# Motherboard.net
KiCad netlist of a schematic drawn in EAGLE
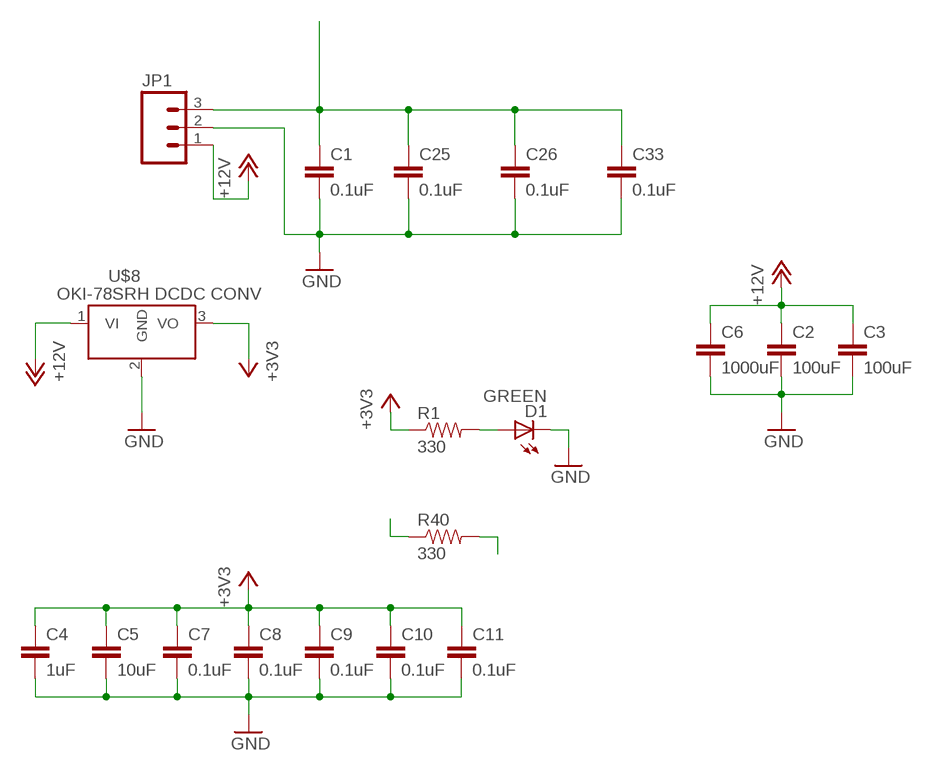
[diagram p0: schematic, sheet 1]
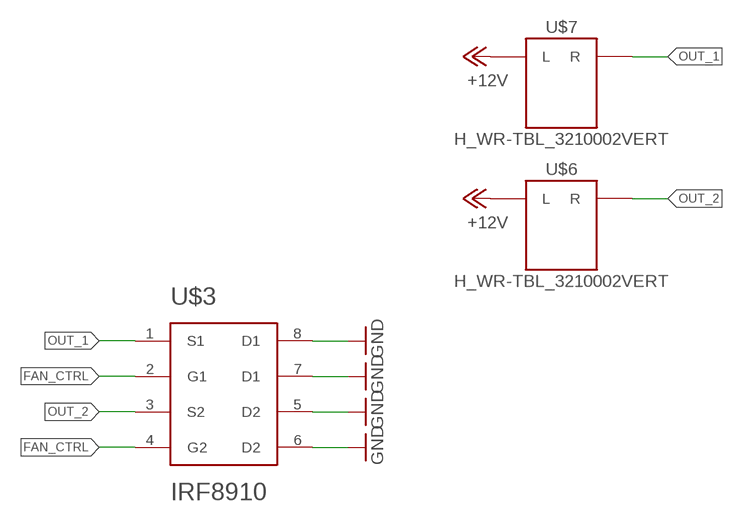
[diagram p1: schematic, sheet 2]
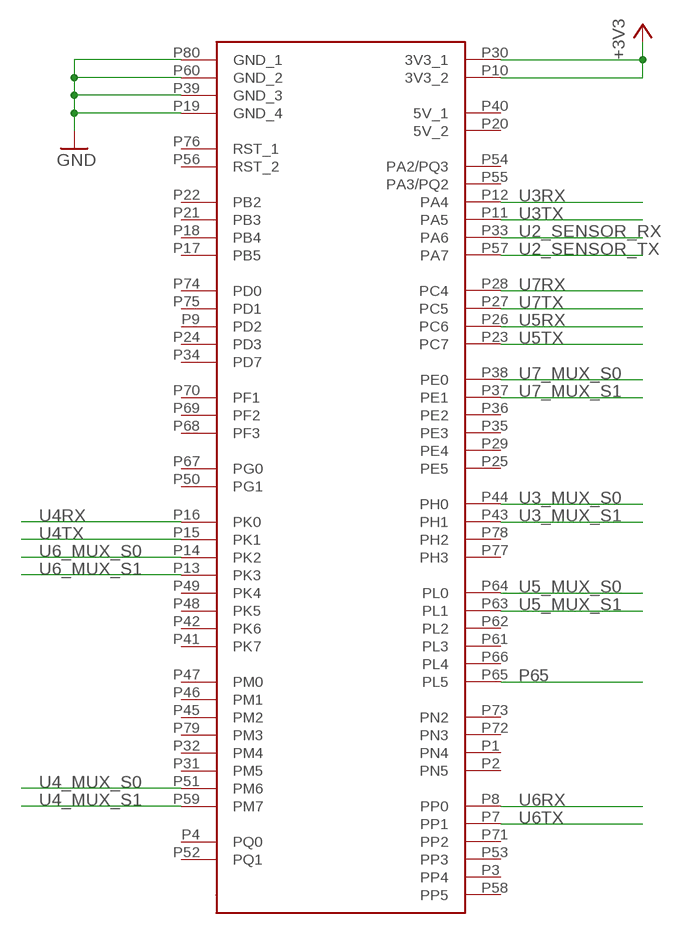
[diagram p2: schematic, sheet 3]
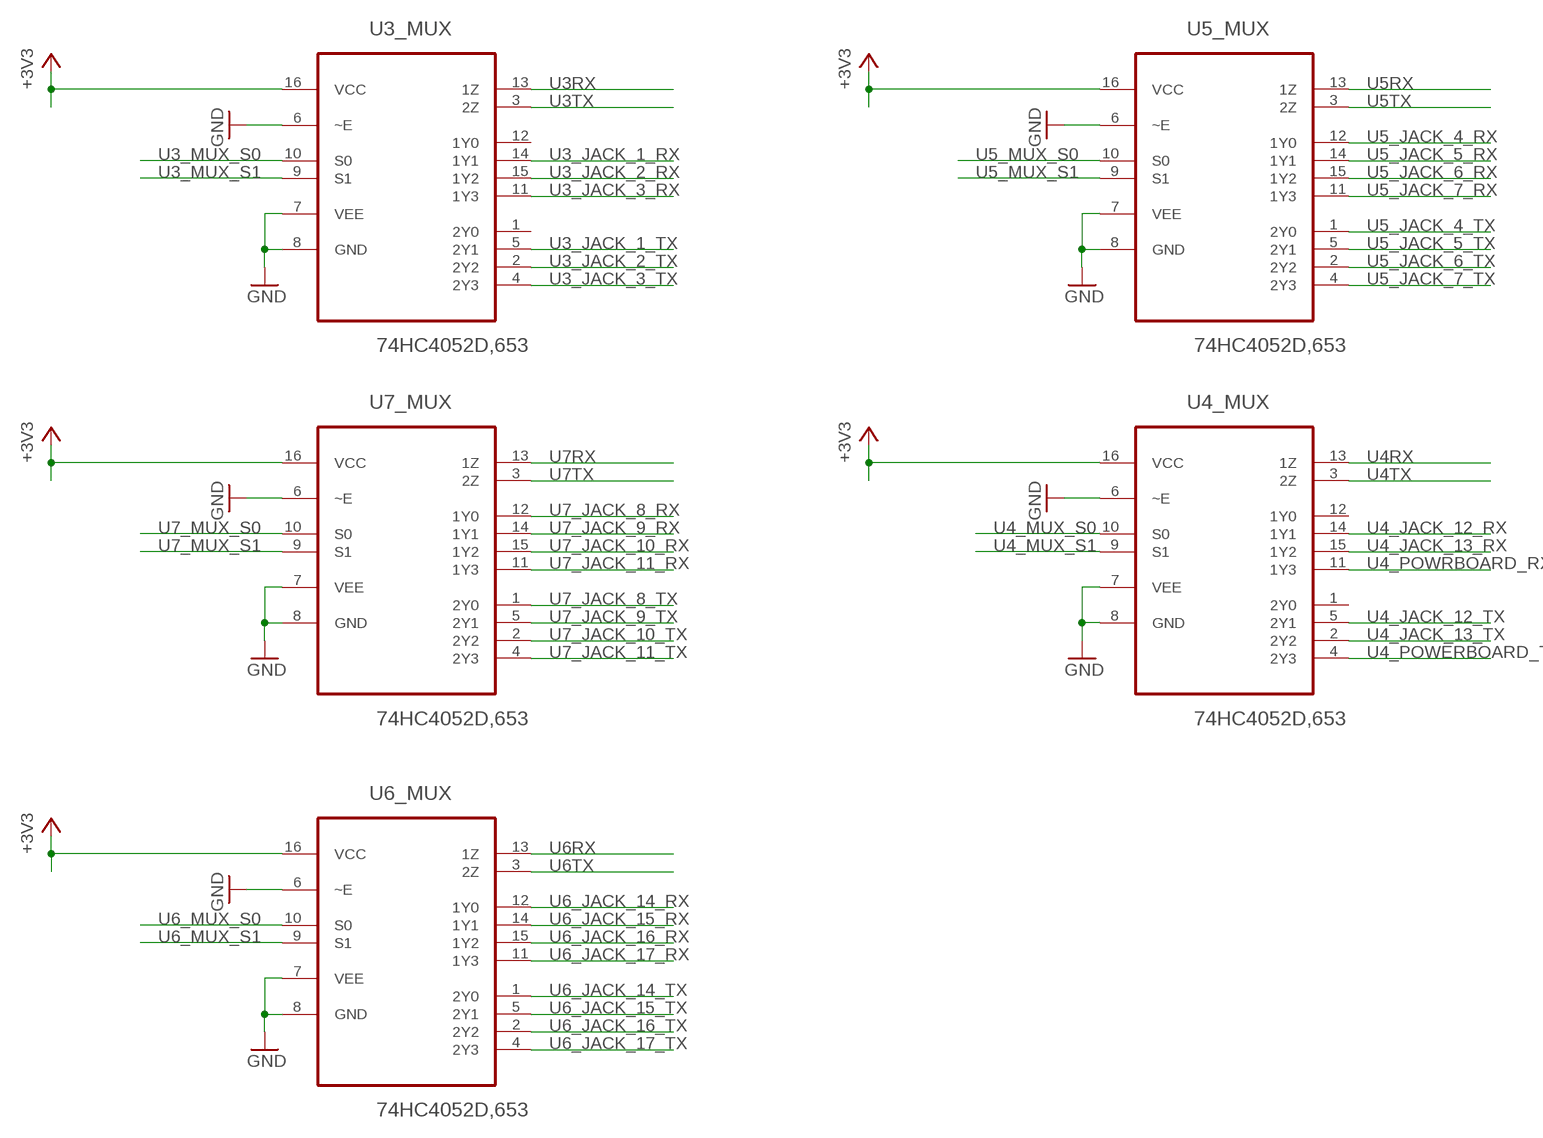
[diagram p3: schematic, sheet 4]
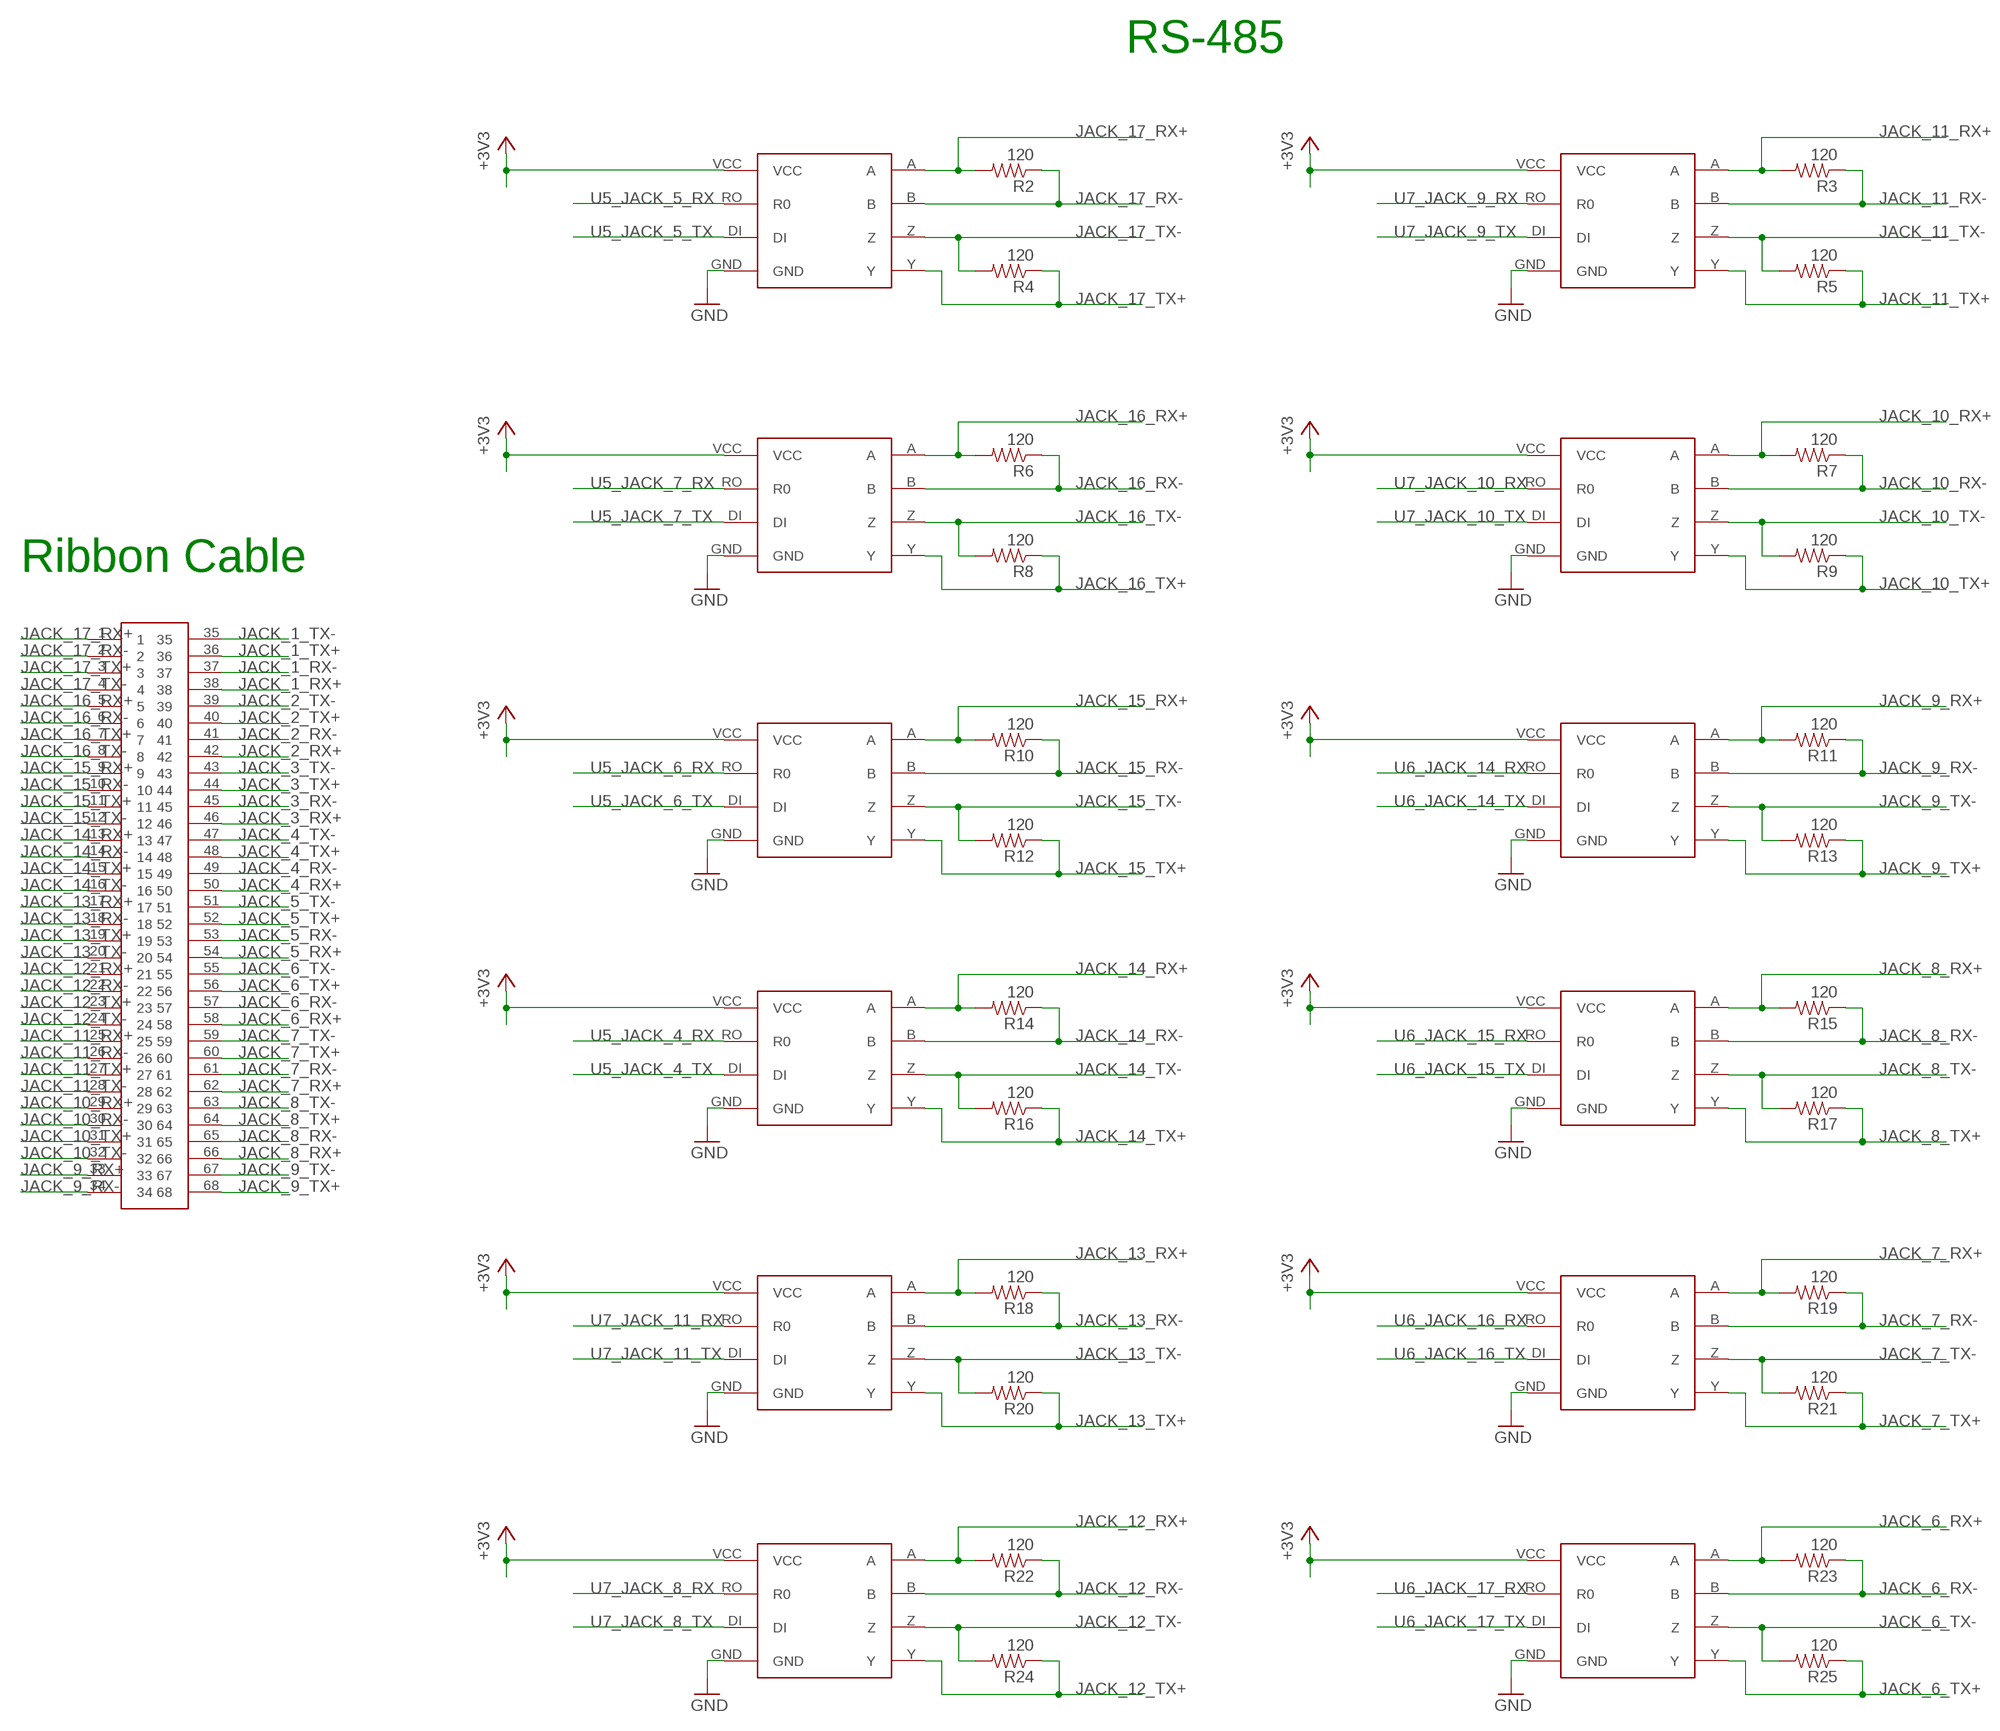
[diagram p4: schematic, sheet 5, part 1 of 2]
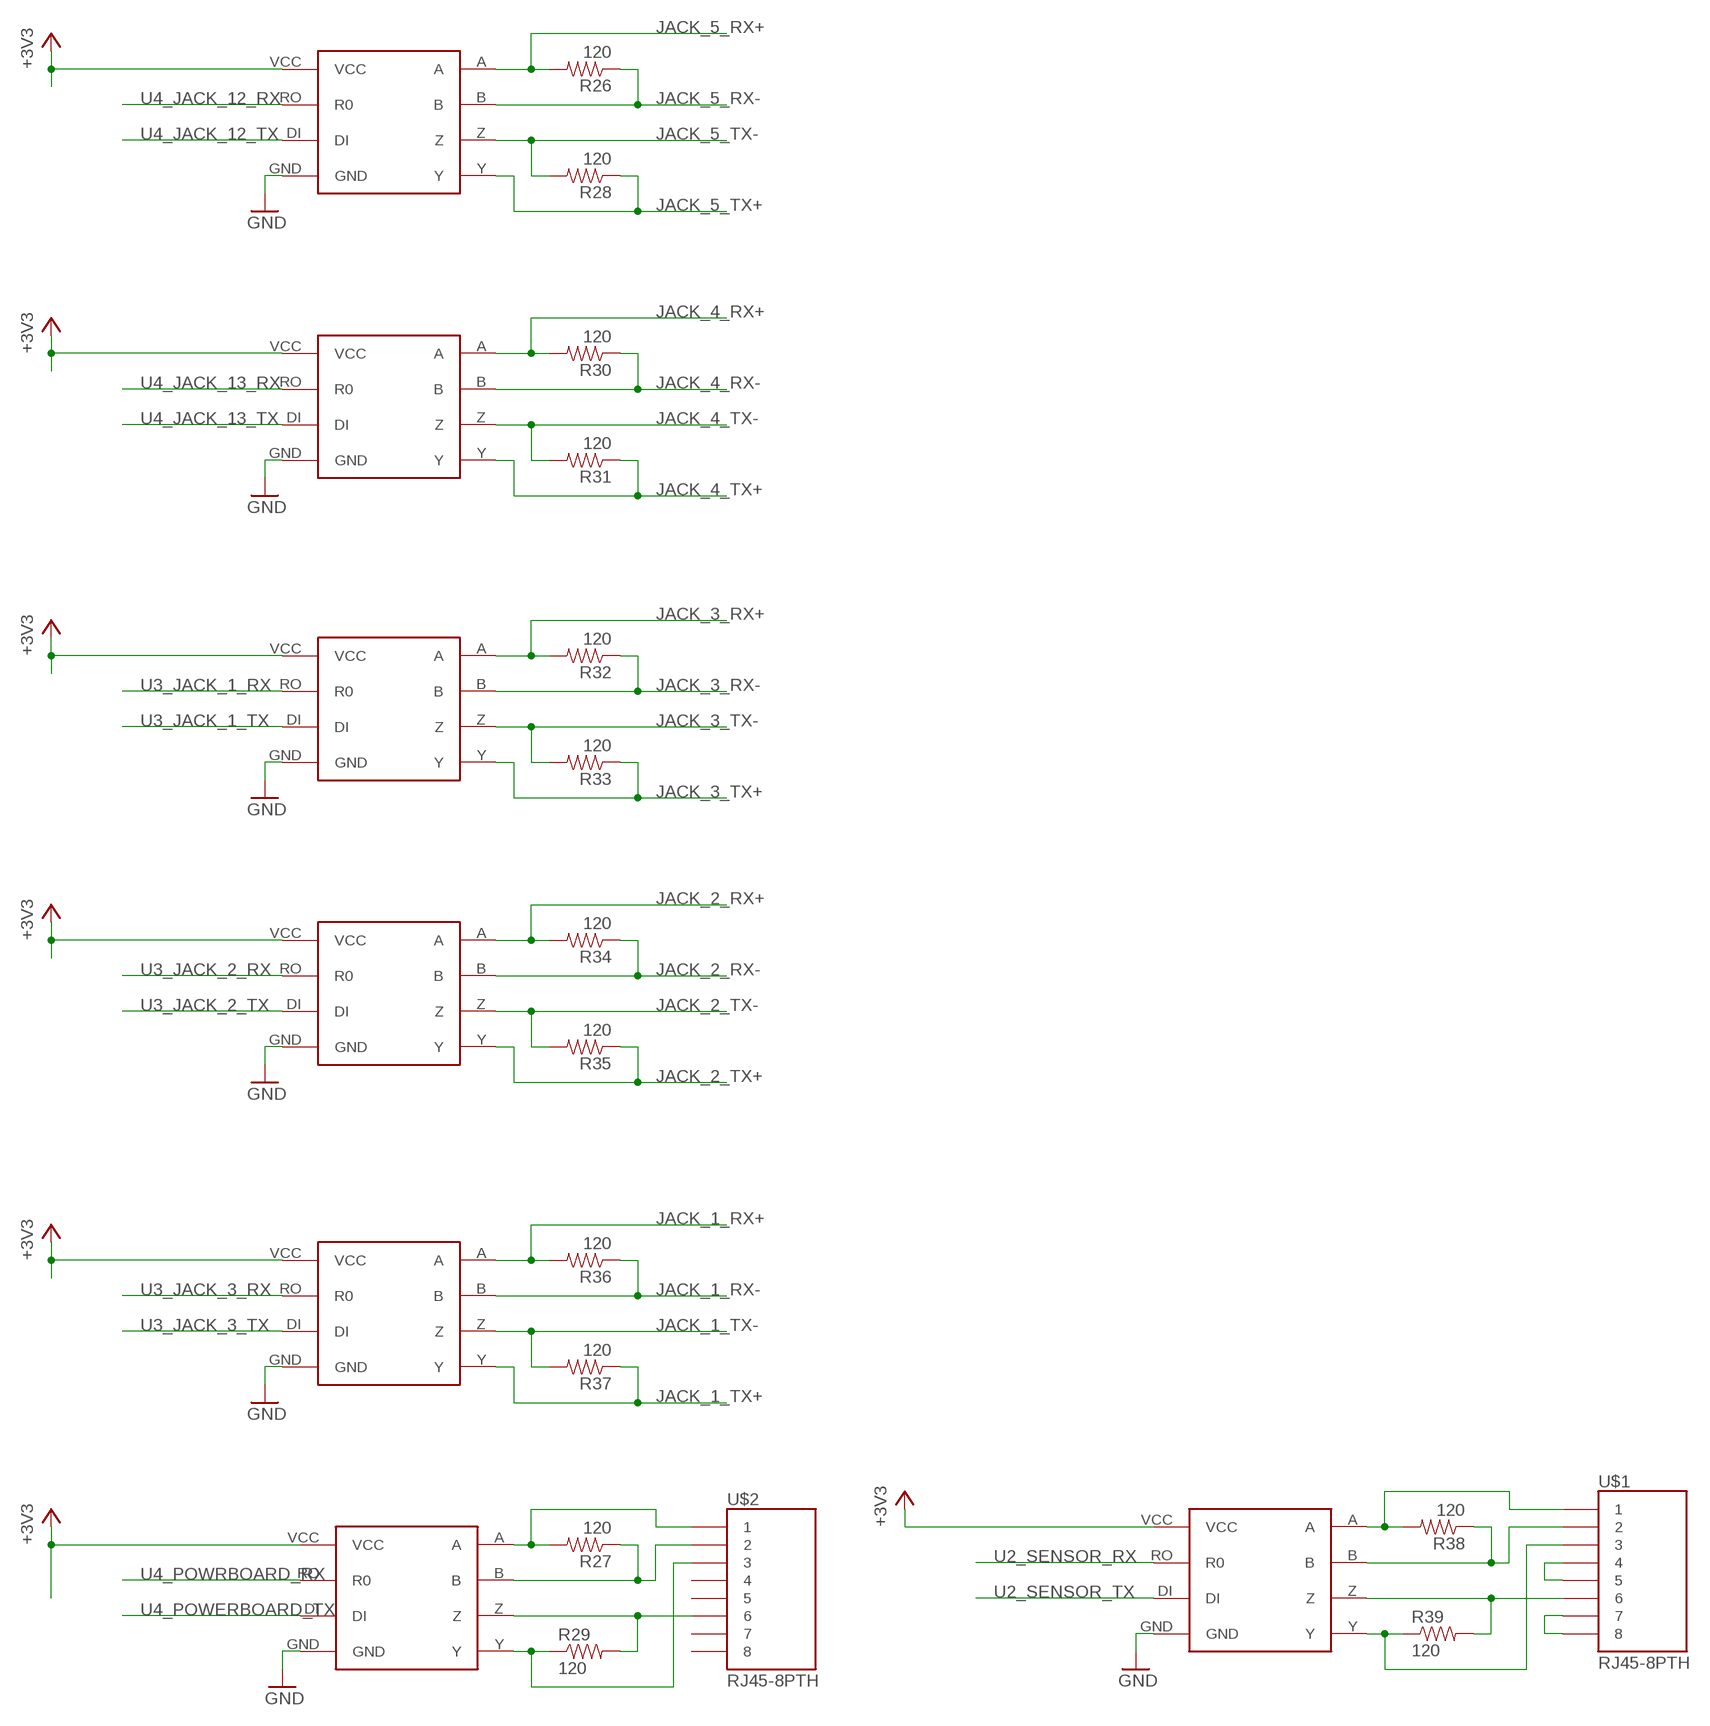
[diagram p5: schematic, sheet 5, part 2 of 2]
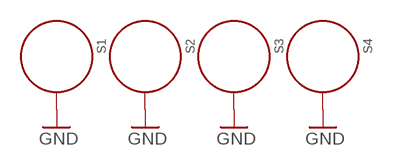
[diagram p6: schematic, sheet 6]

(export (version "E")
  (design (tool "Eeschema 10.0.6"))
  (components
    (comp (ref "S1")
      (value "STANDOFF_ELECTRICAL")
      (footprint "eagle-import:STANDOFF-ELECTRICAL")
      (libsource (lib "eagle-import") (part "STANDOFF_ELECTRICAL"))
    )
    (comp (ref "S2")
      (value "STANDOFF_ELECTRICAL")
      (footprint "eagle-import:STANDOFF-ELECTRICAL")
      (libsource (lib "eagle-import") (part "STANDOFF_ELECTRICAL"))
    )
    (comp (ref "S3")
      (value "STANDOFF_ELECTRICAL")
      (footprint "eagle-import:STANDOFF-ELECTRICAL")
      (libsource (lib "eagle-import") (part "STANDOFF_ELECTRICAL"))
    )
    (comp (ref "S4")
      (value "STANDOFF_ELECTRICAL")
      (footprint "eagle-import:STANDOFF-ELECTRICAL")
      (libsource (lib "eagle-import") (part "STANDOFF_ELECTRICAL"))
    )
    (comp (ref "R2")
      (value "120")
      (footprint "eagle-import:1206")
      (libsource (lib "eagle-import") (part "RESISTOR1206"))
    )
    (comp (ref "R3")
      (value "120")
      (footprint "eagle-import:1206")
      (libsource (lib "eagle-import") (part "RESISTOR1206"))
    )
    (comp (ref "R4")
      (value "120")
      (footprint "eagle-import:1206")
      (libsource (lib "eagle-import") (part "RESISTOR1206"))
    )
    (comp (ref "R5")
      (value "120")
      (footprint "eagle-import:1206")
      (libsource (lib "eagle-import") (part "RESISTOR1206"))
    )
    (comp (ref "R6")
      (value "120")
      (footprint "eagle-import:1206")
      (libsource (lib "eagle-import") (part "RESISTOR1206"))
    )
    (comp (ref "R7")
      (value "120")
      (footprint "eagle-import:1206")
      (libsource (lib "eagle-import") (part "RESISTOR1206"))
    )
    (comp (ref "R8")
      (value "120")
      (footprint "eagle-import:1206")
      (libsource (lib "eagle-import") (part "RESISTOR1206"))
    )
    (comp (ref "R9")
      (value "120")
      (footprint "eagle-import:1206")
      (libsource (lib "eagle-import") (part "RESISTOR1206"))
    )
    (comp (ref "R10")
      (value "120")
      (footprint "eagle-import:1206")
      (libsource (lib "eagle-import") (part "RESISTOR1206"))
    )
    (comp (ref "R11")
      (value "120")
      (footprint "eagle-import:1206")
      (libsource (lib "eagle-import") (part "RESISTOR1206"))
    )
    (comp (ref "R12")
      (value "120")
      (footprint "eagle-import:1206")
      (libsource (lib "eagle-import") (part "RESISTOR1206"))
    )
    (comp (ref "R13")
      (value "120")
      (footprint "eagle-import:1206")
      (libsource (lib "eagle-import") (part "RESISTOR1206"))
    )
    (comp (ref "R14")
      (value "120")
      (footprint "eagle-import:1206")
      (libsource (lib "eagle-import") (part "RESISTOR1206"))
    )
    (comp (ref "R15")
      (value "120")
      (footprint "eagle-import:1206")
      (libsource (lib "eagle-import") (part "RESISTOR1206"))
    )
    (comp (ref "R16")
      (value "120")
      (footprint "eagle-import:1206")
      (libsource (lib "eagle-import") (part "RESISTOR1206"))
    )
    (comp (ref "R17")
      (value "120")
      (footprint "eagle-import:1206")
      (libsource (lib "eagle-import") (part "RESISTOR1206"))
    )
    (comp (ref "R18")
      (value "120")
      (footprint "eagle-import:1206")
      (libsource (lib "eagle-import") (part "RESISTOR1206"))
    )
    (comp (ref "R19")
      (value "120")
      (footprint "eagle-import:1206")
      (libsource (lib "eagle-import") (part "RESISTOR1206"))
    )
    (comp (ref "R20")
      (value "120")
      (footprint "eagle-import:1206")
      (libsource (lib "eagle-import") (part "RESISTOR1206"))
    )
    (comp (ref "R21")
      (value "120")
      (footprint "eagle-import:1206")
      (libsource (lib "eagle-import") (part "RESISTOR1206"))
    )
    (comp (ref "R22")
      (value "120")
      (footprint "eagle-import:1206")
      (libsource (lib "eagle-import") (part "RESISTOR1206"))
    )
    (comp (ref "R23")
      (value "120")
      (footprint "eagle-import:1206")
      (libsource (lib "eagle-import") (part "RESISTOR1206"))
    )
    (comp (ref "R24")
      (value "120")
      (footprint "eagle-import:1206")
      (libsource (lib "eagle-import") (part "RESISTOR1206"))
    )
    (comp (ref "R25")
      (value "120")
      (footprint "eagle-import:1206")
      (libsource (lib "eagle-import") (part "RESISTOR1206"))
    )
    (comp (ref "R26")
      (value "120")
      (footprint "eagle-import:1206")
      (libsource (lib "eagle-import") (part "RESISTOR1206"))
    )
    (comp (ref "R27")
      (value "120")
      (footprint "eagle-import:1206")
      (libsource (lib "eagle-import") (part "RESISTOR1206"))
    )
    (comp (ref "R28")
      (value "120")
      (footprint "eagle-import:1206")
      (libsource (lib "eagle-import") (part "RESISTOR1206"))
    )
    (comp (ref "R29")
      (value "120")
      (footprint "eagle-import:1206")
      (libsource (lib "eagle-import") (part "RESISTOR1206"))
    )
    (comp (ref "R30")
      (value "120")
      (footprint "eagle-import:1206")
      (libsource (lib "eagle-import") (part "RESISTOR1206"))
    )
    (comp (ref "R31")
      (value "120")
      (footprint "eagle-import:1206")
      (libsource (lib "eagle-import") (part "RESISTOR1206"))
    )
    (comp (ref "R32")
      (value "120")
      (footprint "eagle-import:1206")
      (libsource (lib "eagle-import") (part "RESISTOR1206"))
    )
    (comp (ref "R33")
      (value "120")
      (footprint "eagle-import:1206")
      (libsource (lib "eagle-import") (part "RESISTOR1206"))
    )
    (comp (ref "R34")
      (value "120")
      (footprint "eagle-import:1206")
      (libsource (lib "eagle-import") (part "RESISTOR1206"))
    )
    (comp (ref "R35")
      (value "120")
      (footprint "eagle-import:1206")
      (libsource (lib "eagle-import") (part "RESISTOR1206"))
    )
    (comp (ref "R36")
      (value "120")
      (footprint "eagle-import:1206")
      (libsource (lib "eagle-import") (part "RESISTOR1206"))
    )
    (comp (ref "R37")
      (value "120")
      (footprint "eagle-import:1206")
      (libsource (lib "eagle-import") (part "RESISTOR1206"))
    )
    (comp (ref "R38")
      (value "120")
      (footprint "eagle-import:1206")
      (libsource (lib "eagle-import") (part "RESISTOR1206"))
    )
    (comp (ref "R39")
      (value "120")
      (footprint "eagle-import:1206")
      (libsource (lib "eagle-import") (part "RESISTOR1206"))
    )
    (comp (ref "RS-485-1")
      (value "MAX3077")
      (footprint "eagle-import:MAX3070E")
      (libsource (lib "eagle-import") (part "MAX3077"))
    )
    (comp (ref "RS-485-2")
      (value "MAX3077")
      (footprint "eagle-import:MAX3070E")
      (libsource (lib "eagle-import") (part "MAX3077"))
    )
    (comp (ref "RS_TRANS_1")
      (value "MAX3077")
      (footprint "eagle-import:MAX3070E")
      (libsource (lib "eagle-import") (part "MAX3077"))
    )
    (comp (ref "RS_TRANS_2")
      (value "MAX3077")
      (footprint "eagle-import:MAX3070E")
      (libsource (lib "eagle-import") (part "MAX3077"))
    )
    (comp (ref "RS_TRANS_3")
      (value "MAX3077")
      (footprint "eagle-import:MAX3070E")
      (libsource (lib "eagle-import") (part "MAX3077"))
    )
    (comp (ref "RS_TRANS_4")
      (value "MAX3077")
      (footprint "eagle-import:MAX3070E")
      (libsource (lib "eagle-import") (part "MAX3077"))
    )
    (comp (ref "RS_TRANS_5")
      (value "MAX3077")
      (footprint "eagle-import:MAX3070E")
      (libsource (lib "eagle-import") (part "MAX3077"))
    )
    (comp (ref "RS_TRANS_6")
      (value "MAX3077")
      (footprint "eagle-import:MAX3070E")
      (libsource (lib "eagle-import") (part "MAX3077"))
    )
    (comp (ref "RS_TRANS_7")
      (value "MAX3077")
      (footprint "eagle-import:MAX3070E")
      (libsource (lib "eagle-import") (part "MAX3077"))
    )
    (comp (ref "RS_TRANS_8")
      (value "MAX3077")
      (footprint "eagle-import:MAX3070E")
      (libsource (lib "eagle-import") (part "MAX3077"))
    )
    (comp (ref "RS_TRANS_9")
      (value "MAX3077")
      (footprint "eagle-import:MAX3070E")
      (libsource (lib "eagle-import") (part "MAX3077"))
    )
    (comp (ref "RS_TRANS_10")
      (value "MAX3077")
      (footprint "eagle-import:MAX3070E")
      (libsource (lib "eagle-import") (part "MAX3077"))
    )
    (comp (ref "RS_TRANS_11")
      (value "MAX3077")
      (footprint "eagle-import:MAX3070E")
      (libsource (lib "eagle-import") (part "MAX3077"))
    )
    (comp (ref "RS_TRANS_12")
      (value "MAX3077")
      (footprint "eagle-import:MAX3070E")
      (libsource (lib "eagle-import") (part "MAX3077"))
    )
    (comp (ref "RS_TRANS_13")
      (value "MAX3077")
      (footprint "eagle-import:MAX3070E")
      (libsource (lib "eagle-import") (part "MAX3077"))
    )
    (comp (ref "RS_TRANS_14")
      (value "MAX3077")
      (footprint "eagle-import:MAX3070E")
      (libsource (lib "eagle-import") (part "MAX3077"))
    )
    (comp (ref "RS_TRANS_15")
      (value "MAX3077")
      (footprint "eagle-import:MAX3070E")
      (libsource (lib "eagle-import") (part "MAX3077"))
    )
    (comp (ref "RS_TRANS_16")
      (value "MAX3077")
      (footprint "eagle-import:MAX3070E")
      (libsource (lib "eagle-import") (part "MAX3077"))
    )
    (comp (ref "RS_TRANS_17")
      (value "MAX3077")
      (footprint "eagle-import:MAX3070E")
      (libsource (lib "eagle-import") (part "MAX3077"))
    )
    (comp (ref "U$1")
      (value "RJ45-8PTH")
      (footprint "eagle-import:RJ45-8")
      (libsource (lib "eagle-import") (part "RJ45-8PTH"))
    )
    (comp (ref "U$2")
      (value "RJ45-8PTH")
      (footprint "eagle-import:RJ45-8")
      (libsource (lib "eagle-import") (part "RJ45-8PTH"))
    )
    (comp (ref "U$4")
      (value "TB60050685100")
      (footprint "eagle-import:60050685100")
      (libsource (lib "eagle-import") (part "TB60050685100"))
    )
    (comp (ref "C1")
      (value "0.1uF")
      (footprint "eagle-import:1206")
      (libsource (lib "eagle-import") (part "CAP1206"))
    )
    (comp (ref "C2")
      (value "100uF")
      (footprint "eagle-import:1206")
      (libsource (lib "eagle-import") (part "CAP1206"))
    )
    (comp (ref "C3")
      (value "100uF")
      (footprint "eagle-import:1206")
      (libsource (lib "eagle-import") (part "CAP1206"))
    )
    (comp (ref "C4")
      (value "1uF")
      (footprint "eagle-import:1206")
      (libsource (lib "eagle-import") (part "CAP1206"))
    )
    (comp (ref "C5")
      (value "10uF")
      (footprint "eagle-import:1206")
      (libsource (lib "eagle-import") (part "CAP1206"))
    )
    (comp (ref "C6")
      (value "1000uF")
      (footprint "eagle-import:1206")
      (libsource (lib "eagle-import") (part "CAP1206"))
    )
    (comp (ref "C7")
      (value "0.1uF")
      (footprint "eagle-import:1206")
      (libsource (lib "eagle-import") (part "CAP1206"))
    )
    (comp (ref "C8")
      (value "0.1uF")
      (footprint "eagle-import:1206")
      (libsource (lib "eagle-import") (part "CAP1206"))
    )
    (comp (ref "C9")
      (value "0.1uF")
      (footprint "eagle-import:1206")
      (libsource (lib "eagle-import") (part "CAP1206"))
    )
    (comp (ref "C10")
      (value "0.1uF")
      (footprint "eagle-import:1206")
      (libsource (lib "eagle-import") (part "CAP1206"))
    )
    (comp (ref "C11")
      (value "0.1uF")
      (footprint "eagle-import:1206")
      (libsource (lib "eagle-import") (part "CAP1206"))
    )
    (comp (ref "C25")
      (value "0.1uF")
      (footprint "eagle-import:1206")
      (libsource (lib "eagle-import") (part "CAP1206"))
    )
    (comp (ref "C26")
      (value "0.1uF")
      (footprint "eagle-import:1206")
      (libsource (lib "eagle-import") (part "CAP1206"))
    )
    (comp (ref "C33")
      (value "0.1uF")
      (footprint "eagle-import:1206")
      (libsource (lib "eagle-import") (part "CAP1206"))
    )
    (comp (ref "D1")
      (value "GREEN")
      (footprint "eagle-import:LED-1206")
      (libsource (lib "eagle-import") (part "LED-GREENLARGE"))
    )
    (comp (ref "JP1")
      (value "M03SCREW")
      (footprint "eagle-import:SCREWTERMINAL-3.5MM-3")
      (libsource (lib "eagle-import") (part "M03SCREW"))
    )
    (comp (ref "R1")
      (value "330")
      (footprint "eagle-import:1206")
      (libsource (lib "eagle-import") (part "RESISTOR1206"))
    )
    (comp (ref "R40")
      (value "330")
      (footprint "eagle-import:1206")
      (libsource (lib "eagle-import") (part "RESISTOR1206"))
    )
    (comp (ref "U$8")
      (value "Q_OKI-78SR")
      (footprint "eagle-import:OKI-78SRH")
      (libsource (lib "eagle-import") (part "Q_OKI-78SR"))
    )
    (comp (ref "U$3")
      (value "IRF8910")
      (footprint "eagle-import:SO8")
      (libsource (lib "eagle-import") (part "IRF8910"))
    )
    (comp (ref "U$6")
      (value "H_WR-TBL_3210002VERT")
      (footprint "eagle-import:691321100002")
      (libsource (lib "eagle-import") (part "H_WR-TBL_3210002VERT"))
    )
    (comp (ref "U$7")
      (value "H_WR-TBL_3210002VERT")
      (footprint "eagle-import:691321100002")
      (libsource (lib "eagle-import") (part "H_WR-TBL_3210002VERT"))
    )
    (comp (ref "U3_MUX")
      (value "74HC4052D,653")
      (footprint "eagle-import:SOIC127P600X175-16N")
      (libsource (lib "eagle-import") (part "74HC4052D,653"))
    )
    (comp (ref "U4_MUX")
      (value "74HC4052D,653")
      (footprint "eagle-import:SOIC127P600X175-16N")
      (libsource (lib "eagle-import") (part "74HC4052D,653"))
    )
    (comp (ref "U5_MUX")
      (value "74HC4052D,653")
      (footprint "eagle-import:SOIC127P600X175-16N")
      (libsource (lib "eagle-import") (part "74HC4052D,653"))
    )
    (comp (ref "U6_MUX")
      (value "74HC4052D,653")
      (footprint "eagle-import:SOIC127P600X175-16N")
      (libsource (lib "eagle-import") (part "74HC4052D,653"))
    )
    (comp (ref "U7_MUX")
      (value "74HC4052D,653")
      (footprint "eagle-import:SOIC127P600X175-16N")
      (libsource (lib "eagle-import") (part "74HC4052D,653"))
    )
    (comp (ref "U$5")
      (value "STELLARISLAUNCHPAD_CONNECTED")
      (footprint "eagle-import:STELLARISLAUNCHPAD_CONNECTED")
      (libsource (lib "eagle-import") (part "STELLARISLAUNCHPAD_CONNECTED"))
    )
  )
  (nets
    (net (code "1") (name "+3V3") (class "Default")
      (node (ref "C10") (pin "1") (pinfunction "1_1") (pintype "passive"))
      (node (ref "C11") (pin "1") (pinfunction "1_1") (pintype "passive"))
      (node (ref "C4") (pin "1") (pinfunction "1_1") (pintype "passive"))
      (node (ref "C5") (pin "1") (pinfunction "1_1") (pintype "passive"))
      (node (ref "C7") (pin "1") (pinfunction "1_1") (pintype "passive"))
      (node (ref "C8") (pin "1") (pinfunction "1_1") (pintype "passive"))
      (node (ref "C9") (pin "1") (pinfunction "1_1") (pintype "passive"))
      (node (ref "R1") (pin "1") (pinfunction "1_1") (pintype "passive"))
      (node (ref "RS-485-1") (pin "VCC") (pinfunction "VCC_VCC") (pintype "bidirectional"))
      (node (ref "RS-485-2") (pin "VCC") (pinfunction "VCC_VCC") (pintype "bidirectional"))
      (node (ref "RS_TRANS_1") (pin "VCC") (pinfunction "VCC_VCC") (pintype "bidirectional"))
      (node (ref "RS_TRANS_10") (pin "VCC") (pinfunction "VCC_VCC") (pintype "bidirectional"))
      (node (ref "RS_TRANS_11") (pin "VCC") (pinfunction "VCC_VCC") (pintype "bidirectional"))
      (node (ref "RS_TRANS_12") (pin "VCC") (pinfunction "VCC_VCC") (pintype "bidirectional"))
      (node (ref "RS_TRANS_13") (pin "VCC") (pinfunction "VCC_VCC") (pintype "bidirectional"))
      (node (ref "RS_TRANS_14") (pin "VCC") (pinfunction "VCC_VCC") (pintype "bidirectional"))
      (node (ref "RS_TRANS_15") (pin "VCC") (pinfunction "VCC_VCC") (pintype "bidirectional"))
      (node (ref "RS_TRANS_16") (pin "VCC") (pinfunction "VCC_VCC") (pintype "bidirectional"))
      (node (ref "RS_TRANS_17") (pin "VCC") (pinfunction "VCC_VCC") (pintype "bidirectional"))
      (node (ref "RS_TRANS_2") (pin "VCC") (pinfunction "VCC_VCC") (pintype "bidirectional"))
      (node (ref "RS_TRANS_3") (pin "VCC") (pinfunction "VCC_VCC") (pintype "bidirectional"))
      (node (ref "RS_TRANS_4") (pin "VCC") (pinfunction "VCC_VCC") (pintype "bidirectional"))
      (node (ref "RS_TRANS_5") (pin "VCC") (pinfunction "VCC_VCC") (pintype "bidirectional"))
      (node (ref "RS_TRANS_6") (pin "VCC") (pinfunction "VCC_VCC") (pintype "bidirectional"))
      (node (ref "RS_TRANS_7") (pin "VCC") (pinfunction "VCC_VCC") (pintype "bidirectional"))
      (node (ref "RS_TRANS_8") (pin "VCC") (pinfunction "VCC_VCC") (pintype "bidirectional"))
      (node (ref "RS_TRANS_9") (pin "VCC") (pinfunction "VCC_VCC") (pintype "bidirectional"))
      (node (ref "U$5") (pin "P10") (pinfunction "3V3_2_P10") (pintype "bidirectional"))
      (node (ref "U$5") (pin "P30") (pinfunction "3V3_1_P30") (pintype "bidirectional"))
      (node (ref "U$8") (pin "3") (pinfunction "VO_3") (pintype "bidirectional"))
      (node (ref "U3_MUX") (pin "16") (pinfunction "VCC_16") (pintype "power_in"))
      (node (ref "U4_MUX") (pin "16") (pinfunction "VCC_16") (pintype "power_in"))
      (node (ref "U5_MUX") (pin "16") (pinfunction "VCC_16") (pintype "power_in"))
      (node (ref "U6_MUX") (pin "16") (pinfunction "VCC_16") (pintype "power_in"))
      (node (ref "U7_MUX") (pin "16") (pinfunction "VCC_16") (pintype "power_in"))
    )
    (net (code "2") (name "+12V") (class "Default")
      (node (ref "C2") (pin "1") (pinfunction "1_1") (pintype "passive"))
      (node (ref "C3") (pin "1") (pinfunction "1_1") (pintype "passive"))
      (node (ref "C6") (pin "1") (pinfunction "1_1") (pintype "passive"))
      (node (ref "JP1") (pin "1") (pinfunction "1_1") (pintype "passive"))
      (node (ref "U$6") (pin "L") (pinfunction "L_L") (pintype "bidirectional"))
      (node (ref "U$7") (pin "L") (pinfunction "L_L") (pintype "bidirectional"))
      (node (ref "U$8") (pin "1") (pinfunction "VI_1") (pintype "bidirectional"))
    )
    (net (code "3") (name "5V") (class "Default")
      (node (ref "C1") (pin "1") (pinfunction "1_1") (pintype "passive"))
      (node (ref "C25") (pin "1") (pinfunction "1_1") (pintype "passive"))
      (node (ref "C26") (pin "1") (pinfunction "1_1") (pintype "passive"))
      (node (ref "C33") (pin "1") (pinfunction "1_1") (pintype "passive"))
      (node (ref "JP1") (pin "3") (pinfunction "3_3") (pintype "passive"))
      (node (ref "U$1") (pin "4") (pinfunction "4_4") (pintype "bidirectional"))
      (node (ref "U$1") (pin "5") (pinfunction "5_5") (pintype "bidirectional"))
    )
    (net (code "4") (name "FAN_CTRL") (class "Default")
      (node (ref "R40") (pin "2") (pinfunction "2_2") (pintype "passive"))
      (node (ref "U$3") (pin "2") (pinfunction "G1_2") (pintype "bidirectional"))
      (node (ref "U$3") (pin "4") (pinfunction "G2_4") (pintype "bidirectional"))
    )
    (net (code "5") (name "GND") (class "Default")
      (node (ref "C1") (pin "2") (pinfunction "2_2") (pintype "passive"))
      (node (ref "C10") (pin "2") (pinfunction "2_2") (pintype "passive"))
      (node (ref "C11") (pin "2") (pinfunction "2_2") (pintype "passive"))
      (node (ref "C2") (pin "2") (pinfunction "2_2") (pintype "passive"))
      (node (ref "C25") (pin "2") (pinfunction "2_2") (pintype "passive"))
      (node (ref "C26") (pin "2") (pinfunction "2_2") (pintype "passive"))
      (node (ref "C3") (pin "2") (pinfunction "2_2") (pintype "passive"))
      (node (ref "C33") (pin "2") (pinfunction "2_2") (pintype "passive"))
      (node (ref "C4") (pin "2") (pinfunction "2_2") (pintype "passive"))
      (node (ref "C5") (pin "2") (pinfunction "2_2") (pintype "passive"))
      (node (ref "C6") (pin "2") (pinfunction "2_2") (pintype "passive"))
      (node (ref "C7") (pin "2") (pinfunction "2_2") (pintype "passive"))
      (node (ref "C8") (pin "2") (pinfunction "2_2") (pintype "passive"))
      (node (ref "C9") (pin "2") (pinfunction "2_2") (pintype "passive"))
      (node (ref "D1") (pin "C") (pinfunction "C_C") (pintype "passive"))
      (node (ref "JP1") (pin "2") (pinfunction "2_2") (pintype "passive"))
      (node (ref "RS-485-1") (pin "GND") (pinfunction "GND_GND") (pintype "bidirectional"))
      (node (ref "RS-485-2") (pin "GND") (pinfunction "GND_GND") (pintype "bidirectional"))
      (node (ref "RS_TRANS_1") (pin "GND") (pinfunction "GND_GND") (pintype "bidirectional"))
      (node (ref "RS_TRANS_10") (pin "GND") (pinfunction "GND_GND") (pintype "bidirectional"))
      (node (ref "RS_TRANS_11") (pin "GND") (pinfunction "GND_GND") (pintype "bidirectional"))
      (node (ref "RS_TRANS_12") (pin "GND") (pinfunction "GND_GND") (pintype "bidirectional"))
      (node (ref "RS_TRANS_13") (pin "GND") (pinfunction "GND_GND") (pintype "bidirectional"))
      (node (ref "RS_TRANS_14") (pin "GND") (pinfunction "GND_GND") (pintype "bidirectional"))
      (node (ref "RS_TRANS_15") (pin "GND") (pinfunction "GND_GND") (pintype "bidirectional"))
      (node (ref "RS_TRANS_16") (pin "GND") (pinfunction "GND_GND") (pintype "bidirectional"))
      (node (ref "RS_TRANS_17") (pin "GND") (pinfunction "GND_GND") (pintype "bidirectional"))
      (node (ref "RS_TRANS_2") (pin "GND") (pinfunction "GND_GND") (pintype "bidirectional"))
      (node (ref "RS_TRANS_3") (pin "GND") (pinfunction "GND_GND") (pintype "bidirectional"))
      (node (ref "RS_TRANS_4") (pin "GND") (pinfunction "GND_GND") (pintype "bidirectional"))
      (node (ref "RS_TRANS_5") (pin "GND") (pinfunction "GND_GND") (pintype "bidirectional"))
      (node (ref "RS_TRANS_6") (pin "GND") (pinfunction "GND_GND") (pintype "bidirectional"))
      (node (ref "RS_TRANS_7") (pin "GND") (pinfunction "GND_GND") (pintype "bidirectional"))
      (node (ref "RS_TRANS_8") (pin "GND") (pinfunction "GND_GND") (pintype "bidirectional"))
      (node (ref "RS_TRANS_9") (pin "GND") (pinfunction "GND_GND") (pintype "bidirectional"))
      (node (ref "S1") (pin "P1") (pinfunction "P$1_P1") (pintype "bidirectional"))
      (node (ref "S2") (pin "P1") (pinfunction "P$1_P1") (pintype "bidirectional"))
      (node (ref "S3") (pin "P1") (pinfunction "P$1_P1") (pintype "bidirectional"))
      (node (ref "S4") (pin "P1") (pinfunction "P$1_P1") (pintype "bidirectional"))
      (node (ref "U$1") (pin "7") (pinfunction "7_7") (pintype "bidirectional"))
      (node (ref "U$1") (pin "8") (pinfunction "8_8") (pintype "bidirectional"))
      (node (ref "U$3") (pin "5") (pinfunction "D2_5") (pintype "bidirectional"))
      (node (ref "U$3") (pin "6") (pinfunction "D2_6") (pintype "bidirectional"))
      (node (ref "U$3") (pin "7") (pinfunction "D1_7") (pintype "bidirectional"))
      (node (ref "U$3") (pin "8") (pinfunction "D1_8") (pintype "bidirectional"))
      (node (ref "U$5") (pin "P19") (pinfunction "GND_4_P19") (pintype "bidirectional"))
      (node (ref "U$5") (pin "P39") (pinfunction "GND_3_P39") (pintype "bidirectional"))
      (node (ref "U$5") (pin "P60") (pinfunction "GND_2_P60") (pintype "bidirectional"))
      (node (ref "U$5") (pin "P80") (pinfunction "GND_1_P80") (pintype "bidirectional"))
      (node (ref "U$8") (pin "2") (pinfunction "GND_2") (pintype "bidirectional"))
      (node (ref "U3_MUX") (pin "6") (pinfunction "~{E}_6") (pintype "input"))
      (node (ref "U3_MUX") (pin "7") (pinfunction "VEE_7") (pintype "power_in"))
      (node (ref "U3_MUX") (pin "8") (pinfunction "GND_8") (pintype "passive"))
      (node (ref "U4_MUX") (pin "6") (pinfunction "~{E}_6") (pintype "input"))
      (node (ref "U4_MUX") (pin "7") (pinfunction "VEE_7") (pintype "power_in"))
      (node (ref "U4_MUX") (pin "8") (pinfunction "GND_8") (pintype "passive"))
      (node (ref "U5_MUX") (pin "6") (pinfunction "~{E}_6") (pintype "input"))
      (node (ref "U5_MUX") (pin "7") (pinfunction "VEE_7") (pintype "power_in"))
      (node (ref "U5_MUX") (pin "8") (pinfunction "GND_8") (pintype "passive"))
      (node (ref "U6_MUX") (pin "6") (pinfunction "~{E}_6") (pintype "input"))
      (node (ref "U6_MUX") (pin "7") (pinfunction "VEE_7") (pintype "power_in"))
      (node (ref "U6_MUX") (pin "8") (pinfunction "GND_8") (pintype "passive"))
      (node (ref "U7_MUX") (pin "6") (pinfunction "~{E}_6") (pintype "input"))
      (node (ref "U7_MUX") (pin "7") (pinfunction "VEE_7") (pintype "power_in"))
      (node (ref "U7_MUX") (pin "8") (pinfunction "GND_8") (pintype "passive"))
    )
    (net (code "6") (name "JACK_1_RX+") (class "Default")
      (node (ref "R36") (pin "2") (pinfunction "2_2") (pintype "passive"))
      (node (ref "RS_TRANS_17") (pin "A") (pinfunction "A_A") (pintype "bidirectional"))
      (node (ref "U$4") (pin "38") (pinfunction "38_38") (pintype "bidirectional"))
    )
    (net (code "7") (name "JACK_1_RX-") (class "Default")
      (node (ref "R36") (pin "1") (pinfunction "1_1") (pintype "passive"))
      (node (ref "RS_TRANS_17") (pin "B") (pinfunction "B_B") (pintype "bidirectional"))
      (node (ref "U$4") (pin "37") (pinfunction "37_37") (pintype "bidirectional"))
    )
    (net (code "8") (name "JACK_1_TX+") (class "Default")
      (node (ref "R37") (pin "1") (pinfunction "1_1") (pintype "passive"))
      (node (ref "RS_TRANS_17") (pin "Y") (pinfunction "Y_Y") (pintype "bidirectional"))
      (node (ref "U$4") (pin "36") (pinfunction "36_36") (pintype "bidirectional"))
    )
    (net (code "9") (name "JACK_1_TX-") (class "Default")
      (node (ref "R37") (pin "2") (pinfunction "2_2") (pintype "passive"))
      (node (ref "RS_TRANS_17") (pin "Z") (pinfunction "Z_Z") (pintype "bidirectional"))
      (node (ref "U$4") (pin "35") (pinfunction "35_35") (pintype "bidirectional"))
    )
    (net (code "10") (name "JACK_2_RX+") (class "Default")
      (node (ref "R34") (pin "2") (pinfunction "2_2") (pintype "passive"))
      (node (ref "RS_TRANS_16") (pin "A") (pinfunction "A_A") (pintype "bidirectional"))
      (node (ref "U$4") (pin "42") (pinfunction "42_42") (pintype "bidirectional"))
    )
    (net (code "11") (name "JACK_2_RX-") (class "Default")
      (node (ref "R34") (pin "1") (pinfunction "1_1") (pintype "passive"))
      (node (ref "RS_TRANS_16") (pin "B") (pinfunction "B_B") (pintype "bidirectional"))
      (node (ref "U$4") (pin "41") (pinfunction "41_41") (pintype "bidirectional"))
    )
    (net (code "12") (name "JACK_2_TX+") (class "Default")
      (node (ref "R35") (pin "1") (pinfunction "1_1") (pintype "passive"))
      (node (ref "RS_TRANS_16") (pin "Y") (pinfunction "Y_Y") (pintype "bidirectional"))
      (node (ref "U$4") (pin "40") (pinfunction "40_40") (pintype "bidirectional"))
    )
    (net (code "13") (name "JACK_2_TX-") (class "Default")
      (node (ref "R35") (pin "2") (pinfunction "2_2") (pintype "passive"))
      (node (ref "RS_TRANS_16") (pin "Z") (pinfunction "Z_Z") (pintype "bidirectional"))
      (node (ref "U$4") (pin "39") (pinfunction "39_39") (pintype "bidirectional"))
    )
    (net (code "14") (name "JACK_3_RX+") (class "Default")
      (node (ref "R32") (pin "2") (pinfunction "2_2") (pintype "passive"))
      (node (ref "RS_TRANS_15") (pin "A") (pinfunction "A_A") (pintype "bidirectional"))
      (node (ref "U$4") (pin "46") (pinfunction "46_46") (pintype "bidirectional"))
    )
    (net (code "15") (name "JACK_3_RX-") (class "Default")
      (node (ref "R32") (pin "1") (pinfunction "1_1") (pintype "passive"))
      (node (ref "RS_TRANS_15") (pin "B") (pinfunction "B_B") (pintype "bidirectional"))
      (node (ref "U$4") (pin "45") (pinfunction "45_45") (pintype "bidirectional"))
    )
    (net (code "16") (name "JACK_3_TX+") (class "Default")
      (node (ref "R33") (pin "1") (pinfunction "1_1") (pintype "passive"))
      (node (ref "RS_TRANS_15") (pin "Y") (pinfunction "Y_Y") (pintype "bidirectional"))
      (node (ref "U$4") (pin "44") (pinfunction "44_44") (pintype "bidirectional"))
    )
    (net (code "17") (name "JACK_3_TX-") (class "Default")
      (node (ref "R33") (pin "2") (pinfunction "2_2") (pintype "passive"))
      (node (ref "RS_TRANS_15") (pin "Z") (pinfunction "Z_Z") (pintype "bidirectional"))
      (node (ref "U$4") (pin "43") (pinfunction "43_43") (pintype "bidirectional"))
    )
    (net (code "18") (name "JACK_4_RX+") (class "Default")
      (node (ref "R30") (pin "2") (pinfunction "2_2") (pintype "passive"))
      (node (ref "RS_TRANS_14") (pin "A") (pinfunction "A_A") (pintype "bidirectional"))
      (node (ref "U$4") (pin "50") (pinfunction "50_50") (pintype "bidirectional"))
    )
    (net (code "19") (name "JACK_4_RX-") (class "Default")
      (node (ref "R30") (pin "1") (pinfunction "1_1") (pintype "passive"))
      (node (ref "RS_TRANS_14") (pin "B") (pinfunction "B_B") (pintype "bidirectional"))
      (node (ref "U$4") (pin "49") (pinfunction "49_49") (pintype "bidirectional"))
    )
    (net (code "20") (name "JACK_4_TX+") (class "Default")
      (node (ref "R31") (pin "1") (pinfunction "1_1") (pintype "passive"))
      (node (ref "RS_TRANS_14") (pin "Y") (pinfunction "Y_Y") (pintype "bidirectional"))
      (node (ref "U$4") (pin "48") (pinfunction "48_48") (pintype "bidirectional"))
    )
    (net (code "21") (name "JACK_4_TX-") (class "Default")
      (node (ref "R31") (pin "2") (pinfunction "2_2") (pintype "passive"))
      (node (ref "RS_TRANS_14") (pin "Z") (pinfunction "Z_Z") (pintype "bidirectional"))
      (node (ref "U$4") (pin "47") (pinfunction "47_47") (pintype "bidirectional"))
    )
    (net (code "22") (name "JACK_5_RX+") (class "Default")
      (node (ref "R26") (pin "2") (pinfunction "2_2") (pintype "passive"))
      (node (ref "RS_TRANS_13") (pin "A") (pinfunction "A_A") (pintype "bidirectional"))
      (node (ref "U$4") (pin "54") (pinfunction "54_54") (pintype "bidirectional"))
    )
    (net (code "23") (name "JACK_5_RX-") (class "Default")
      (node (ref "R26") (pin "1") (pinfunction "1_1") (pintype "passive"))
      (node (ref "RS_TRANS_13") (pin "B") (pinfunction "B_B") (pintype "bidirectional"))
      (node (ref "U$4") (pin "53") (pinfunction "53_53") (pintype "bidirectional"))
    )
    (net (code "24") (name "JACK_5_TX+") (class "Default")
      (node (ref "R28") (pin "1") (pinfunction "1_1") (pintype "passive"))
      (node (ref "RS_TRANS_13") (pin "Y") (pinfunction "Y_Y") (pintype "bidirectional"))
      (node (ref "U$4") (pin "52") (pinfunction "52_52") (pintype "bidirectional"))
    )
    (net (code "25") (name "JACK_5_TX-") (class "Default")
      (node (ref "R28") (pin "2") (pinfunction "2_2") (pintype "passive"))
      (node (ref "RS_TRANS_13") (pin "Z") (pinfunction "Z_Z") (pintype "bidirectional"))
      (node (ref "U$4") (pin "51") (pinfunction "51_51") (pintype "bidirectional"))
    )
    (net (code "26") (name "JACK_6_RX+") (class "Default")
      (node (ref "R23") (pin "2") (pinfunction "2_2") (pintype "passive"))
      (node (ref "RS_TRANS_12") (pin "A") (pinfunction "A_A") (pintype "bidirectional"))
      (node (ref "U$4") (pin "58") (pinfunction "58_58") (pintype "bidirectional"))
    )
    (net (code "27") (name "JACK_6_RX-") (class "Default")
      (node (ref "R23") (pin "1") (pinfunction "1_1") (pintype "passive"))
      (node (ref "RS_TRANS_12") (pin "B") (pinfunction "B_B") (pintype "bidirectional"))
      (node (ref "U$4") (pin "57") (pinfunction "57_57") (pintype "bidirectional"))
    )
    (net (code "28") (name "JACK_6_TX+") (class "Default")
      (node (ref "R25") (pin "1") (pinfunction "1_1") (pintype "passive"))
      (node (ref "RS_TRANS_12") (pin "Y") (pinfunction "Y_Y") (pintype "bidirectional"))
      (node (ref "U$4") (pin "56") (pinfunction "56_56") (pintype "bidirectional"))
    )
    (net (code "29") (name "JACK_6_TX-") (class "Default")
      (node (ref "R25") (pin "2") (pinfunction "2_2") (pintype "passive"))
      (node (ref "RS_TRANS_12") (pin "Z") (pinfunction "Z_Z") (pintype "bidirectional"))
      (node (ref "U$4") (pin "55") (pinfunction "55_55") (pintype "bidirectional"))
    )
    (net (code "30") (name "JACK_7_RX+") (class "Default")
      (node (ref "R19") (pin "2") (pinfunction "2_2") (pintype "passive"))
      (node (ref "RS_TRANS_10") (pin "A") (pinfunction "A_A") (pintype "bidirectional"))
      (node (ref "U$4") (pin "62") (pinfunction "62_62") (pintype "bidirectional"))
    )
    (net (code "31") (name "JACK_7_RX-") (class "Default")
      (node (ref "R19") (pin "1") (pinfunction "1_1") (pintype "passive"))
      (node (ref "RS_TRANS_10") (pin "B") (pinfunction "B_B") (pintype "bidirectional"))
      (node (ref "U$4") (pin "61") (pinfunction "61_61") (pintype "bidirectional"))
    )
    (net (code "32") (name "JACK_7_TX+") (class "Default")
      (node (ref "R21") (pin "1") (pinfunction "1_1") (pintype "passive"))
      (node (ref "RS_TRANS_10") (pin "Y") (pinfunction "Y_Y") (pintype "bidirectional"))
      (node (ref "U$4") (pin "60") (pinfunction "60_60") (pintype "bidirectional"))
    )
    (net (code "33") (name "JACK_7_TX-") (class "Default")
      (node (ref "R21") (pin "2") (pinfunction "2_2") (pintype "passive"))
      (node (ref "RS_TRANS_10") (pin "Z") (pinfunction "Z_Z") (pintype "bidirectional"))
      (node (ref "U$4") (pin "59") (pinfunction "59_59") (pintype "bidirectional"))
    )
    (net (code "34") (name "JACK_8_RX+") (class "Default")
      (node (ref "R15") (pin "2") (pinfunction "2_2") (pintype "passive"))
      (node (ref "RS_TRANS_8") (pin "A") (pinfunction "A_A") (pintype "bidirectional"))
      (node (ref "U$4") (pin "66") (pinfunction "66_66") (pintype "bidirectional"))
    )
    (net (code "35") (name "JACK_8_RX-") (class "Default")
      (node (ref "R15") (pin "1") (pinfunction "1_1") (pintype "passive"))
      (node (ref "RS_TRANS_8") (pin "B") (pinfunction "B_B") (pintype "bidirectional"))
      (node (ref "U$4") (pin "65") (pinfunction "65_65") (pintype "bidirectional"))
    )
    (net (code "36") (name "JACK_8_TX+") (class "Default")
      (node (ref "R17") (pin "1") (pinfunction "1_1") (pintype "passive"))
      (node (ref "RS_TRANS_8") (pin "Y") (pinfunction "Y_Y") (pintype "bidirectional"))
      (node (ref "U$4") (pin "64") (pinfunction "64_64") (pintype "bidirectional"))
    )
    (net (code "37") (name "JACK_8_TX-") (class "Default")
      (node (ref "R17") (pin "2") (pinfunction "2_2") (pintype "passive"))
      (node (ref "RS_TRANS_8") (pin "Z") (pinfunction "Z_Z") (pintype "bidirectional"))
      (node (ref "U$4") (pin "63") (pinfunction "63_63") (pintype "bidirectional"))
    )
    (net (code "38") (name "JACK_9_RX+") (class "Default")
      (node (ref "R11") (pin "2") (pinfunction "2_2") (pintype "passive"))
      (node (ref "RS_TRANS_6") (pin "A") (pinfunction "A_A") (pintype "bidirectional"))
      (node (ref "U$4") (pin "33") (pinfunction "33_33") (pintype "bidirectional"))
    )
    (net (code "39") (name "JACK_9_RX-") (class "Default")
      (node (ref "R11") (pin "1") (pinfunction "1_1") (pintype "passive"))
      (node (ref "RS_TRANS_6") (pin "B") (pinfunction "B_B") (pintype "bidirectional"))
      (node (ref "U$4") (pin "34") (pinfunction "34_34") (pintype "bidirectional"))
    )
    (net (code "40") (name "JACK_9_TX+") (class "Default")
      (node (ref "R13") (pin "1") (pinfunction "1_1") (pintype "passive"))
      (node (ref "RS_TRANS_6") (pin "Y") (pinfunction "Y_Y") (pintype "bidirectional"))
      (node (ref "U$4") (pin "68") (pinfunction "68_68") (pintype "bidirectional"))
    )
    (net (code "41") (name "JACK_9_TX-") (class "Default")
      (node (ref "R13") (pin "2") (pinfunction "2_2") (pintype "passive"))
      (node (ref "RS_TRANS_6") (pin "Z") (pinfunction "Z_Z") (pintype "bidirectional"))
      (node (ref "U$4") (pin "67") (pinfunction "67_67") (pintype "bidirectional"))
    )
    (net (code "42") (name "JACK_10_RX+") (class "Default")
      (node (ref "R7") (pin "2") (pinfunction "2_2") (pintype "passive"))
      (node (ref "RS_TRANS_4") (pin "A") (pinfunction "A_A") (pintype "bidirectional"))
      (node (ref "U$4") (pin "29") (pinfunction "29_29") (pintype "bidirectional"))
    )
    (net (code "43") (name "JACK_10_RX-") (class "Default")
      (node (ref "R7") (pin "1") (pinfunction "1_1") (pintype "passive"))
      (node (ref "RS_TRANS_4") (pin "B") (pinfunction "B_B") (pintype "bidirectional"))
      (node (ref "U$4") (pin "30") (pinfunction "30_30") (pintype "bidirectional"))
    )
    (net (code "44") (name "JACK_10_TX+") (class "Default")
      (node (ref "R9") (pin "1") (pinfunction "1_1") (pintype "passive"))
      (node (ref "RS_TRANS_4") (pin "Y") (pinfunction "Y_Y") (pintype "bidirectional"))
      (node (ref "U$4") (pin "31") (pinfunction "31_31") (pintype "bidirectional"))
    )
    (net (code "45") (name "JACK_10_TX-") (class "Default")
      (node (ref "R9") (pin "2") (pinfunction "2_2") (pintype "passive"))
      (node (ref "RS_TRANS_4") (pin "Z") (pinfunction "Z_Z") (pintype "bidirectional"))
      (node (ref "U$4") (pin "32") (pinfunction "32_32") (pintype "bidirectional"))
    )
    (net (code "46") (name "JACK_11_RX+") (class "Default")
      (node (ref "R3") (pin "2") (pinfunction "2_2") (pintype "passive"))
      (node (ref "RS_TRANS_2") (pin "A") (pinfunction "A_A") (pintype "bidirectional"))
      (node (ref "U$4") (pin "25") (pinfunction "25_25") (pintype "bidirectional"))
    )
    (net (code "47") (name "JACK_11_RX-") (class "Default")
      (node (ref "R3") (pin "1") (pinfunction "1_1") (pintype "passive"))
      (node (ref "RS_TRANS_2") (pin "B") (pinfunction "B_B") (pintype "bidirectional"))
      (node (ref "U$4") (pin "26") (pinfunction "26_26") (pintype "bidirectional"))
    )
    (net (code "48") (name "JACK_11_TX+") (class "Default")
      (node (ref "R5") (pin "1") (pinfunction "1_1") (pintype "passive"))
      (node (ref "RS_TRANS_2") (pin "Y") (pinfunction "Y_Y") (pintype "bidirectional"))
      (node (ref "U$4") (pin "27") (pinfunction "27_27") (pintype "bidirectional"))
    )
    (net (code "49") (name "JACK_11_TX-") (class "Default")
      (node (ref "R5") (pin "2") (pinfunction "2_2") (pintype "passive"))
      (node (ref "RS_TRANS_2") (pin "Z") (pinfunction "Z_Z") (pintype "bidirectional"))
      (node (ref "U$4") (pin "28") (pinfunction "28_28") (pintype "bidirectional"))
    )
    (net (code "50") (name "JACK_12_RX+") (class "Default")
      (node (ref "R22") (pin "2") (pinfunction "2_2") (pintype "passive"))
      (node (ref "RS_TRANS_11") (pin "A") (pinfunction "A_A") (pintype "bidirectional"))
      (node (ref "U$4") (pin "21") (pinfunction "21_21") (pintype "bidirectional"))
    )
    (net (code "51") (name "JACK_12_RX-") (class "Default")
      (node (ref "R22") (pin "1") (pinfunction "1_1") (pintype "passive"))
      (node (ref "RS_TRANS_11") (pin "B") (pinfunction "B_B") (pintype "bidirectional"))
      (node (ref "U$4") (pin "22") (pinfunction "22_22") (pintype "bidirectional"))
    )
    (net (code "52") (name "JACK_12_TX+") (class "Default")
      (node (ref "R24") (pin "1") (pinfunction "1_1") (pintype "passive"))
      (node (ref "RS_TRANS_11") (pin "Y") (pinfunction "Y_Y") (pintype "bidirectional"))
      (node (ref "U$4") (pin "23") (pinfunction "23_23") (pintype "bidirectional"))
    )
    (net (code "53") (name "JACK_12_TX-") (class "Default")
      (node (ref "R24") (pin "2") (pinfunction "2_2") (pintype "passive"))
      (node (ref "RS_TRANS_11") (pin "Z") (pinfunction "Z_Z") (pintype "bidirectional"))
      (node (ref "U$4") (pin "24") (pinfunction "24_24") (pintype "bidirectional"))
    )
    (net (code "54") (name "JACK_13_RX+") (class "Default")
      (node (ref "R18") (pin "2") (pinfunction "2_2") (pintype "passive"))
      (node (ref "RS_TRANS_9") (pin "A") (pinfunction "A_A") (pintype "bidirectional"))
      (node (ref "U$4") (pin "17") (pinfunction "17_17") (pintype "bidirectional"))
    )
    (net (code "55") (name "JACK_13_RX-") (class "Default")
      (node (ref "R18") (pin "1") (pinfunction "1_1") (pintype "passive"))
      (node (ref "RS_TRANS_9") (pin "B") (pinfunction "B_B") (pintype "bidirectional"))
      (node (ref "U$4") (pin "18") (pinfunction "18_18") (pintype "bidirectional"))
    )
    (net (code "56") (name "JACK_13_TX+") (class "Default")
      (node (ref "R20") (pin "1") (pinfunction "1_1") (pintype "passive"))
      (node (ref "RS_TRANS_9") (pin "Y") (pinfunction "Y_Y") (pintype "bidirectional"))
      (node (ref "U$4") (pin "19") (pinfunction "19_19") (pintype "bidirectional"))
    )
    (net (code "57") (name "JACK_13_TX-") (class "Default")
      (node (ref "R20") (pin "2") (pinfunction "2_2") (pintype "passive"))
      (node (ref "RS_TRANS_9") (pin "Z") (pinfunction "Z_Z") (pintype "bidirectional"))
      (node (ref "U$4") (pin "20") (pinfunction "20_20") (pintype "bidirectional"))
    )
    (net (code "58") (name "JACK_14_RX+") (class "Default")
      (node (ref "R14") (pin "2") (pinfunction "2_2") (pintype "passive"))
      (node (ref "RS_TRANS_7") (pin "A") (pinfunction "A_A") (pintype "bidirectional"))
      (node (ref "U$4") (pin "13") (pinfunction "13_13") (pintype "bidirectional"))
    )
    (net (code "59") (name "JACK_14_RX-") (class "Default")
      (node (ref "R14") (pin "1") (pinfunction "1_1") (pintype "passive"))
      (node (ref "RS_TRANS_7") (pin "B") (pinfunction "B_B") (pintype "bidirectional"))
      (node (ref "U$4") (pin "14") (pinfunction "14_14") (pintype "bidirectional"))
    )
    (net (code "60") (name "JACK_14_TX+") (class "Default")
      (node (ref "R16") (pin "1") (pinfunction "1_1") (pintype "passive"))
      (node (ref "RS_TRANS_7") (pin "Y") (pinfunction "Y_Y") (pintype "bidirectional"))
      (node (ref "U$4") (pin "15") (pinfunction "15_15") (pintype "bidirectional"))
    )
    (net (code "61") (name "JACK_14_TX-") (class "Default")
      (node (ref "R16") (pin "2") (pinfunction "2_2") (pintype "passive"))
      (node (ref "RS_TRANS_7") (pin "Z") (pinfunction "Z_Z") (pintype "bidirectional"))
      (node (ref "U$4") (pin "16") (pinfunction "16_16") (pintype "bidirectional"))
    )
    (net (code "62") (name "JACK_15_RX+") (class "Default")
      (node (ref "R10") (pin "2") (pinfunction "2_2") (pintype "passive"))
      (node (ref "RS_TRANS_5") (pin "A") (pinfunction "A_A") (pintype "bidirectional"))
      (node (ref "U$4") (pin "9") (pinfunction "9_9") (pintype "bidirectional"))
    )
    (net (code "63") (name "JACK_15_RX-") (class "Default")
      (node (ref "R10") (pin "1") (pinfunction "1_1") (pintype "passive"))
      (node (ref "RS_TRANS_5") (pin "B") (pinfunction "B_B") (pintype "bidirectional"))
      (node (ref "U$4") (pin "10") (pinfunction "10_10") (pintype "bidirectional"))
    )
    (net (code "64") (name "JACK_15_TX+") (class "Default")
      (node (ref "R12") (pin "1") (pinfunction "1_1") (pintype "passive"))
      (node (ref "RS_TRANS_5") (pin "Y") (pinfunction "Y_Y") (pintype "bidirectional"))
      (node (ref "U$4") (pin "11") (pinfunction "11_11") (pintype "bidirectional"))
    )
    (net (code "65") (name "JACK_15_TX-") (class "Default")
      (node (ref "R12") (pin "2") (pinfunction "2_2") (pintype "passive"))
      (node (ref "RS_TRANS_5") (pin "Z") (pinfunction "Z_Z") (pintype "bidirectional"))
      (node (ref "U$4") (pin "12") (pinfunction "12_12") (pintype "bidirectional"))
    )
    (net (code "66") (name "JACK_16_RX+") (class "Default")
      (node (ref "R6") (pin "2") (pinfunction "2_2") (pintype "passive"))
      (node (ref "RS_TRANS_3") (pin "A") (pinfunction "A_A") (pintype "bidirectional"))
      (node (ref "U$4") (pin "5") (pinfunction "5_5") (pintype "bidirectional"))
    )
    (net (code "67") (name "JACK_16_RX-") (class "Default")
      (node (ref "R6") (pin "1") (pinfunction "1_1") (pintype "passive"))
      (node (ref "RS_TRANS_3") (pin "B") (pinfunction "B_B") (pintype "bidirectional"))
      (node (ref "U$4") (pin "6") (pinfunction "6_6") (pintype "bidirectional"))
    )
    (net (code "68") (name "JACK_16_TX+") (class "Default")
      (node (ref "R8") (pin "1") (pinfunction "1_1") (pintype "passive"))
      (node (ref "RS_TRANS_3") (pin "Y") (pinfunction "Y_Y") (pintype "bidirectional"))
      (node (ref "U$4") (pin "7") (pinfunction "7_7") (pintype "bidirectional"))
    )
    (net (code "69") (name "JACK_16_TX-") (class "Default")
      (node (ref "R8") (pin "2") (pinfunction "2_2") (pintype "passive"))
      (node (ref "RS_TRANS_3") (pin "Z") (pinfunction "Z_Z") (pintype "bidirectional"))
      (node (ref "U$4") (pin "8") (pinfunction "8_8") (pintype "bidirectional"))
    )
    (net (code "70") (name "JACK_17_RX+") (class "Default")
      (node (ref "R2") (pin "2") (pinfunction "2_2") (pintype "passive"))
      (node (ref "RS_TRANS_1") (pin "A") (pinfunction "A_A") (pintype "bidirectional"))
      (node (ref "U$4") (pin "1") (pinfunction "1_1") (pintype "bidirectional"))
    )
    (net (code "71") (name "JACK_17_RX-") (class "Default")
      (node (ref "R2") (pin "1") (pinfunction "1_1") (pintype "passive"))
      (node (ref "RS_TRANS_1") (pin "B") (pinfunction "B_B") (pintype "bidirectional"))
      (node (ref "U$4") (pin "2") (pinfunction "2_2") (pintype "bidirectional"))
    )
    (net (code "72") (name "JACK_17_TX+") (class "Default")
      (node (ref "R4") (pin "1") (pinfunction "1_1") (pintype "passive"))
      (node (ref "RS_TRANS_1") (pin "Y") (pinfunction "Y_Y") (pintype "bidirectional"))
      (node (ref "U$4") (pin "3") (pinfunction "3_3") (pintype "bidirectional"))
    )
    (net (code "73") (name "JACK_17_TX-") (class "Default")
      (node (ref "R4") (pin "2") (pinfunction "2_2") (pintype "passive"))
      (node (ref "RS_TRANS_1") (pin "Z") (pinfunction "Z_Z") (pintype "bidirectional"))
      (node (ref "U$4") (pin "4") (pinfunction "4_4") (pintype "bidirectional"))
    )
    (net (code "74") (name "Net-(D1-PadA)") (class "Default")
      (node (ref "D1") (pin "A") (pinfunction "A_A") (pintype "passive"))
      (node (ref "R1") (pin "2") (pinfunction "2_2") (pintype "passive"))
    )
    (net (code "75") (name "Net-(R27-Pad1)") (class "Default")
      (node (ref "R27") (pin "1") (pinfunction "1_1") (pintype "passive"))
      (node (ref "RS-485-2") (pin "B") (pinfunction "B_B") (pintype "bidirectional"))
      (node (ref "U$2") (pin "2") (pinfunction "2_2") (pintype "bidirectional"))
    )
    (net (code "76") (name "Net-(R27-Pad2)") (class "Default")
      (node (ref "R27") (pin "2") (pinfunction "2_2") (pintype "passive"))
      (node (ref "RS-485-2") (pin "A") (pinfunction "A_A") (pintype "bidirectional"))
      (node (ref "U$2") (pin "1") (pinfunction "1_1") (pintype "bidirectional"))
    )
    (net (code "77") (name "Net-(R29-Pad1)") (class "Default")
      (node (ref "R29") (pin "1") (pinfunction "1_1") (pintype "passive"))
      (node (ref "RS-485-2") (pin "Y") (pinfunction "Y_Y") (pintype "bidirectional"))
      (node (ref "U$2") (pin "3") (pinfunction "3_3") (pintype "bidirectional"))
    )
    (net (code "78") (name "Net-(R29-Pad2)") (class "Default")
      (node (ref "R29") (pin "2") (pinfunction "2_2") (pintype "passive"))
      (node (ref "RS-485-2") (pin "Z") (pinfunction "Z_Z") (pintype "bidirectional"))
      (node (ref "U$2") (pin "6") (pinfunction "6_6") (pintype "bidirectional"))
    )
    (net (code "79") (name "Net-(R38-Pad1)") (class "Default")
      (node (ref "R38") (pin "1") (pinfunction "1_1") (pintype "passive"))
      (node (ref "RS-485-1") (pin "B") (pinfunction "B_B") (pintype "bidirectional"))
      (node (ref "U$1") (pin "2") (pinfunction "2_2") (pintype "bidirectional"))
    )
    (net (code "80") (name "Net-(R38-Pad2)") (class "Default")
      (node (ref "R38") (pin "2") (pinfunction "2_2") (pintype "passive"))
      (node (ref "RS-485-1") (pin "A") (pinfunction "A_A") (pintype "bidirectional"))
      (node (ref "U$1") (pin "1") (pinfunction "1_1") (pintype "bidirectional"))
    )
    (net (code "81") (name "Net-(R39-Pad1)") (class "Default")
      (node (ref "R39") (pin "1") (pinfunction "1_1") (pintype "passive"))
      (node (ref "RS-485-1") (pin "Y") (pinfunction "Y_Y") (pintype "bidirectional"))
      (node (ref "U$1") (pin "3") (pinfunction "3_3") (pintype "bidirectional"))
    )
    (net (code "82") (name "Net-(R39-Pad2)") (class "Default")
      (node (ref "R39") (pin "2") (pinfunction "2_2") (pintype "passive"))
      (node (ref "RS-485-1") (pin "Z") (pinfunction "Z_Z") (pintype "bidirectional"))
      (node (ref "U$1") (pin "6") (pinfunction "6_6") (pintype "bidirectional"))
    )
    (net (code "83") (name "OUT_1") (class "Default")
      (node (ref "U$3") (pin "1") (pinfunction "S1_1") (pintype "bidirectional"))
      (node (ref "U$7") (pin "R") (pinfunction "R_R") (pintype "bidirectional"))
    )
    (net (code "84") (name "OUT_2") (class "Default")
      (node (ref "U$3") (pin "3") (pinfunction "S2_3") (pintype "bidirectional"))
      (node (ref "U$6") (pin "R") (pinfunction "R_R") (pintype "bidirectional"))
    )
    (net (code "85") (name "P65") (class "Default")
      (node (ref "R40") (pin "1") (pinfunction "1_1") (pintype "passive"))
      (node (ref "U$5") (pin "P65") (pinfunction "PL5_P65") (pintype "bidirectional"))
    )
    (net (code "86") (name "U2_SENSOR_RX") (class "Default")
      (node (ref "RS-485-1") (pin "RO") (pinfunction "R0_RO") (pintype "bidirectional"))
      (node (ref "U$5") (pin "P33") (pinfunction "PA6_P33") (pintype "bidirectional"))
    )
    (net (code "87") (name "U2_SENSOR_TX") (class "Default")
      (node (ref "RS-485-1") (pin "DI") (pinfunction "DI_DI") (pintype "bidirectional"))
      (node (ref "U$5") (pin "P57") (pinfunction "PA7_P57") (pintype "bidirectional"))
    )
    (net (code "88") (name "U3RX") (class "Default")
      (node (ref "U$5") (pin "P12") (pinfunction "PA4_P12") (pintype "bidirectional"))
      (node (ref "U3_MUX") (pin "13") (pinfunction "1Z_13") (pintype "bidirectional"))
    )
    (net (code "89") (name "U3TX") (class "Default")
      (node (ref "U$5") (pin "P11") (pinfunction "PA5_P11") (pintype "bidirectional"))
      (node (ref "U3_MUX") (pin "3") (pinfunction "2Z_3") (pintype "bidirectional"))
    )
    (net (code "90") (name "U3_JACK_1_RX") (class "Default")
      (node (ref "RS_TRANS_15") (pin "RO") (pinfunction "R0_RO") (pintype "bidirectional"))
      (node (ref "U3_MUX") (pin "14") (pinfunction "1Y1_14") (pintype "bidirectional"))
    )
    (net (code "91") (name "U3_JACK_1_TX") (class "Default")
      (node (ref "RS_TRANS_15") (pin "DI") (pinfunction "DI_DI") (pintype "bidirectional"))
      (node (ref "U3_MUX") (pin "5") (pinfunction "2Y1_5") (pintype "bidirectional"))
    )
    (net (code "92") (name "U3_JACK_2_RX") (class "Default")
      (node (ref "RS_TRANS_16") (pin "RO") (pinfunction "R0_RO") (pintype "bidirectional"))
      (node (ref "U3_MUX") (pin "15") (pinfunction "1Y2_15") (pintype "bidirectional"))
    )
    (net (code "93") (name "U3_JACK_2_TX") (class "Default")
      (node (ref "RS_TRANS_16") (pin "DI") (pinfunction "DI_DI") (pintype "bidirectional"))
      (node (ref "U3_MUX") (pin "2") (pinfunction "2Y2_2") (pintype "bidirectional"))
    )
    (net (code "94") (name "U3_JACK_3_RX") (class "Default")
      (node (ref "RS_TRANS_17") (pin "RO") (pinfunction "R0_RO") (pintype "bidirectional"))
      (node (ref "U3_MUX") (pin "11") (pinfunction "1Y3_11") (pintype "bidirectional"))
    )
    (net (code "95") (name "U3_JACK_3_TX") (class "Default")
      (node (ref "RS_TRANS_17") (pin "DI") (pinfunction "DI_DI") (pintype "bidirectional"))
      (node (ref "U3_MUX") (pin "4") (pinfunction "2Y3_4") (pintype "bidirectional"))
    )
    (net (code "96") (name "U3_MUX_S0") (class "Default")
      (node (ref "U$5") (pin "P44") (pinfunction "PH0_P44") (pintype "bidirectional"))
      (node (ref "U3_MUX") (pin "10") (pinfunction "S0_10") (pintype "input"))
    )
    (net (code "97") (name "U3_MUX_S1") (class "Default")
      (node (ref "U$5") (pin "P43") (pinfunction "PH1_P43") (pintype "bidirectional"))
      (node (ref "U3_MUX") (pin "9") (pinfunction "S1_9") (pintype "input"))
    )
    (net (code "98") (name "U4RX") (class "Default")
      (node (ref "U$5") (pin "P16") (pinfunction "PK0_P16") (pintype "bidirectional"))
      (node (ref "U4_MUX") (pin "13") (pinfunction "1Z_13") (pintype "bidirectional"))
    )
    (net (code "99") (name "U4TX") (class "Default")
      (node (ref "U$5") (pin "P15") (pinfunction "PK1_P15") (pintype "bidirectional"))
      (node (ref "U4_MUX") (pin "3") (pinfunction "2Z_3") (pintype "bidirectional"))
    )
    (net (code "100") (name "U4_JACK_12_RX") (class "Default")
      (node (ref "RS_TRANS_13") (pin "RO") (pinfunction "R0_RO") (pintype "bidirectional"))
      (node (ref "U4_MUX") (pin "14") (pinfunction "1Y1_14") (pintype "bidirectional"))
    )
    (net (code "101") (name "U4_JACK_12_TX") (class "Default")
      (node (ref "RS_TRANS_13") (pin "DI") (pinfunction "DI_DI") (pintype "bidirectional"))
      (node (ref "U4_MUX") (pin "5") (pinfunction "2Y1_5") (pintype "bidirectional"))
    )
    (net (code "102") (name "U4_JACK_13_RX") (class "Default")
      (node (ref "RS_TRANS_14") (pin "RO") (pinfunction "R0_RO") (pintype "bidirectional"))
      (node (ref "U4_MUX") (pin "15") (pinfunction "1Y2_15") (pintype "bidirectional"))
    )
    (net (code "103") (name "U4_JACK_13_TX") (class "Default")
      (node (ref "RS_TRANS_14") (pin "DI") (pinfunction "DI_DI") (pintype "bidirectional"))
      (node (ref "U4_MUX") (pin "2") (pinfunction "2Y2_2") (pintype "bidirectional"))
    )
    (net (code "104") (name "U4_MUX_S0") (class "Default")
      (node (ref "U$5") (pin "P51") (pinfunction "PM6_P51") (pintype "bidirectional"))
      (node (ref "U4_MUX") (pin "10") (pinfunction "S0_10") (pintype "input"))
    )
    (net (code "105") (name "U4_MUX_S1") (class "Default")
      (node (ref "U$5") (pin "P59") (pinfunction "PM7_P59") (pintype "bidirectional"))
      (node (ref "U4_MUX") (pin "9") (pinfunction "S1_9") (pintype "input"))
    )
    (net (code "106") (name "U4_POWERBOARD_TX") (class "Default")
      (node (ref "RS-485-2") (pin "DI") (pinfunction "DI_DI") (pintype "bidirectional"))
      (node (ref "U4_MUX") (pin "4") (pinfunction "2Y3_4") (pintype "bidirectional"))
    )
    (net (code "107") (name "U4_POWRBOARD_RX") (class "Default")
      (node (ref "RS-485-2") (pin "RO") (pinfunction "R0_RO") (pintype "bidirectional"))
      (node (ref "U4_MUX") (pin "11") (pinfunction "1Y3_11") (pintype "bidirectional"))
    )
    (net (code "108") (name "U5RX") (class "Default")
      (node (ref "U$5") (pin "P26") (pinfunction "PC6_P26") (pintype "bidirectional"))
      (node (ref "U5_MUX") (pin "13") (pinfunction "1Z_13") (pintype "bidirectional"))
    )
    (net (code "109") (name "U5TX") (class "Default")
      (node (ref "U$5") (pin "P23") (pinfunction "PC7_P23") (pintype "bidirectional"))
      (node (ref "U5_MUX") (pin "3") (pinfunction "2Z_3") (pintype "bidirectional"))
    )
    (net (code "110") (name "U5_JACK_4_RX") (class "Default")
      (node (ref "RS_TRANS_7") (pin "RO") (pinfunction "R0_RO") (pintype "bidirectional"))
      (node (ref "U5_MUX") (pin "12") (pinfunction "1Y0_12") (pintype "bidirectional"))
    )
    (net (code "111") (name "U5_JACK_4_TX") (class "Default")
      (node (ref "RS_TRANS_7") (pin "DI") (pinfunction "DI_DI") (pintype "bidirectional"))
      (node (ref "U5_MUX") (pin "1") (pinfunction "2Y0_1") (pintype "bidirectional"))
    )
    (net (code "112") (name "U5_JACK_5_RX") (class "Default")
      (node (ref "RS_TRANS_1") (pin "RO") (pinfunction "R0_RO") (pintype "bidirectional"))
      (node (ref "U5_MUX") (pin "14") (pinfunction "1Y1_14") (pintype "bidirectional"))
    )
    (net (code "113") (name "U5_JACK_5_TX") (class "Default")
      (node (ref "RS_TRANS_1") (pin "DI") (pinfunction "DI_DI") (pintype "bidirectional"))
      (node (ref "U5_MUX") (pin "5") (pinfunction "2Y1_5") (pintype "bidirectional"))
    )
    (net (code "114") (name "U5_JACK_6_RX") (class "Default")
      (node (ref "RS_TRANS_5") (pin "RO") (pinfunction "R0_RO") (pintype "bidirectional"))
      (node (ref "U5_MUX") (pin "15") (pinfunction "1Y2_15") (pintype "bidirectional"))
    )
    (net (code "115") (name "U5_JACK_6_TX") (class "Default")
      (node (ref "RS_TRANS_5") (pin "DI") (pinfunction "DI_DI") (pintype "bidirectional"))
      (node (ref "U5_MUX") (pin "2") (pinfunction "2Y2_2") (pintype "bidirectional"))
    )
    (net (code "116") (name "U5_JACK_7_RX") (class "Default")
      (node (ref "RS_TRANS_3") (pin "RO") (pinfunction "R0_RO") (pintype "bidirectional"))
      (node (ref "U5_MUX") (pin "11") (pinfunction "1Y3_11") (pintype "bidirectional"))
    )
    (net (code "117") (name "U5_JACK_7_TX") (class "Default")
      (node (ref "RS_TRANS_3") (pin "DI") (pinfunction "DI_DI") (pintype "bidirectional"))
      (node (ref "U5_MUX") (pin "4") (pinfunction "2Y3_4") (pintype "bidirectional"))
    )
    (net (code "118") (name "U5_MUX_S0") (class "Default")
      (node (ref "U$5") (pin "P64") (pinfunction "PL0_P64") (pintype "bidirectional"))
      (node (ref "U5_MUX") (pin "10") (pinfunction "S0_10") (pintype "input"))
    )
    (net (code "119") (name "U5_MUX_S1") (class "Default")
      (node (ref "U$5") (pin "P63") (pinfunction "PL1_P63") (pintype "bidirectional"))
      (node (ref "U5_MUX") (pin "9") (pinfunction "S1_9") (pintype "input"))
    )
    (net (code "120") (name "U6RX") (class "Default")
      (node (ref "U$5") (pin "P8") (pinfunction "PP0_P8") (pintype "bidirectional"))
      (node (ref "U6_MUX") (pin "13") (pinfunction "1Z_13") (pintype "bidirectional"))
    )
    (net (code "121") (name "U6TX") (class "Default")
      (node (ref "U$5") (pin "P7") (pinfunction "PP1_P7") (pintype "bidirectional"))
      (node (ref "U6_MUX") (pin "3") (pinfunction "2Z_3") (pintype "bidirectional"))
    )
    (net (code "122") (name "U6_JACK_14_RX") (class "Default")
      (node (ref "RS_TRANS_6") (pin "RO") (pinfunction "R0_RO") (pintype "bidirectional"))
      (node (ref "U6_MUX") (pin "12") (pinfunction "1Y0_12") (pintype "bidirectional"))
    )
    (net (code "123") (name "U6_JACK_14_TX") (class "Default")
      (node (ref "RS_TRANS_6") (pin "DI") (pinfunction "DI_DI") (pintype "bidirectional"))
      (node (ref "U6_MUX") (pin "1") (pinfunction "2Y0_1") (pintype "bidirectional"))
    )
    (net (code "124") (name "U6_JACK_15_RX") (class "Default")
      (node (ref "RS_TRANS_8") (pin "RO") (pinfunction "R0_RO") (pintype "bidirectional"))
      (node (ref "U6_MUX") (pin "14") (pinfunction "1Y1_14") (pintype "bidirectional"))
    )
    (net (code "125") (name "U6_JACK_15_TX") (class "Default")
      (node (ref "RS_TRANS_8") (pin "DI") (pinfunction "DI_DI") (pintype "bidirectional"))
      (node (ref "U6_MUX") (pin "5") (pinfunction "2Y1_5") (pintype "bidirectional"))
    )
    (net (code "126") (name "U6_JACK_16_RX") (class "Default")
      (node (ref "RS_TRANS_10") (pin "RO") (pinfunction "R0_RO") (pintype "bidirectional"))
      (node (ref "U6_MUX") (pin "15") (pinfunction "1Y2_15") (pintype "bidirectional"))
    )
    (net (code "127") (name "U6_JACK_16_TX") (class "Default")
      (node (ref "RS_TRANS_10") (pin "DI") (pinfunction "DI_DI") (pintype "bidirectional"))
      (node (ref "U6_MUX") (pin "2") (pinfunction "2Y2_2") (pintype "bidirectional"))
    )
    (net (code "128") (name "U6_JACK_17_RX") (class "Default")
      (node (ref "RS_TRANS_12") (pin "RO") (pinfunction "R0_RO") (pintype "bidirectional"))
      (node (ref "U6_MUX") (pin "11") (pinfunction "1Y3_11") (pintype "bidirectional"))
    )
    (net (code "129") (name "U6_JACK_17_TX") (class "Default")
      (node (ref "RS_TRANS_12") (pin "DI") (pinfunction "DI_DI") (pintype "bidirectional"))
      (node (ref "U6_MUX") (pin "4") (pinfunction "2Y3_4") (pintype "bidirectional"))
    )
    (net (code "130") (name "U6_MUX_S0") (class "Default")
      (node (ref "U$5") (pin "P14") (pinfunction "PK2_P14") (pintype "bidirectional"))
      (node (ref "U6_MUX") (pin "10") (pinfunction "S0_10") (pintype "input"))
    )
    (net (code "131") (name "U6_MUX_S1") (class "Default")
      (node (ref "U$5") (pin "P13") (pinfunction "PK3_P13") (pintype "bidirectional"))
      (node (ref "U6_MUX") (pin "9") (pinfunction "S1_9") (pintype "input"))
    )
    (net (code "132") (name "U7RX") (class "Default")
      (node (ref "U$5") (pin "P28") (pinfunction "PC4_P28") (pintype "bidirectional"))
      (node (ref "U7_MUX") (pin "13") (pinfunction "1Z_13") (pintype "bidirectional"))
    )
    (net (code "133") (name "U7TX") (class "Default")
      (node (ref "U$5") (pin "P27") (pinfunction "PC5_P27") (pintype "bidirectional"))
      (node (ref "U7_MUX") (pin "3") (pinfunction "2Z_3") (pintype "bidirectional"))
    )
    (net (code "134") (name "U7_JACK_8_RX") (class "Default")
      (node (ref "RS_TRANS_11") (pin "RO") (pinfunction "R0_RO") (pintype "bidirectional"))
      (node (ref "U7_MUX") (pin "12") (pinfunction "1Y0_12") (pintype "bidirectional"))
    )
    (net (code "135") (name "U7_JACK_8_TX") (class "Default")
      (node (ref "RS_TRANS_11") (pin "DI") (pinfunction "DI_DI") (pintype "bidirectional"))
      (node (ref "U7_MUX") (pin "1") (pinfunction "2Y0_1") (pintype "bidirectional"))
    )
    (net (code "136") (name "U7_JACK_9_RX") (class "Default")
      (node (ref "RS_TRANS_2") (pin "RO") (pinfunction "R0_RO") (pintype "bidirectional"))
      (node (ref "U7_MUX") (pin "14") (pinfunction "1Y1_14") (pintype "bidirectional"))
    )
    (net (code "137") (name "U7_JACK_9_TX") (class "Default")
      (node (ref "RS_TRANS_2") (pin "DI") (pinfunction "DI_DI") (pintype "bidirectional"))
      (node (ref "U7_MUX") (pin "5") (pinfunction "2Y1_5") (pintype "bidirectional"))
    )
    (net (code "138") (name "U7_JACK_10_RX") (class "Default")
      (node (ref "RS_TRANS_4") (pin "RO") (pinfunction "R0_RO") (pintype "bidirectional"))
      (node (ref "U7_MUX") (pin "15") (pinfunction "1Y2_15") (pintype "bidirectional"))
    )
    (net (code "139") (name "U7_JACK_10_TX") (class "Default")
      (node (ref "RS_TRANS_4") (pin "DI") (pinfunction "DI_DI") (pintype "bidirectional"))
      (node (ref "U7_MUX") (pin "2") (pinfunction "2Y2_2") (pintype "bidirectional"))
    )
    (net (code "140") (name "U7_JACK_11_RX") (class "Default")
      (node (ref "RS_TRANS_9") (pin "RO") (pinfunction "R0_RO") (pintype "bidirectional"))
      (node (ref "U7_MUX") (pin "11") (pinfunction "1Y3_11") (pintype "bidirectional"))
    )
    (net (code "141") (name "U7_JACK_11_TX") (class "Default")
      (node (ref "RS_TRANS_9") (pin "DI") (pinfunction "DI_DI") (pintype "bidirectional"))
      (node (ref "U7_MUX") (pin "4") (pinfunction "2Y3_4") (pintype "bidirectional"))
    )
    (net (code "142") (name "U7_MUX_S0") (class "Default")
      (node (ref "U$5") (pin "P38") (pinfunction "PE0_P38") (pintype "bidirectional"))
      (node (ref "U7_MUX") (pin "10") (pinfunction "S0_10") (pintype "input"))
    )
    (net (code "143") (name "U7_MUX_S1") (class "Default")
      (node (ref "U$5") (pin "P37") (pinfunction "PE1_P37") (pintype "bidirectional"))
      (node (ref "U7_MUX") (pin "9") (pinfunction "S1_9") (pintype "input"))
    )
    (net (code "144") (name "unconnected-(U$2-Pad4)") (class "Default")
      (node (ref "U$2") (pin "4") (pinfunction "4_4") (pintype "bidirectional"))
    )
    (net (code "145") (name "unconnected-(U$2-Pad5)") (class "Default")
      (node (ref "U$2") (pin "5") (pinfunction "5_5") (pintype "bidirectional"))
    )
    (net (code "146") (name "unconnected-(U$2-Pad7)") (class "Default")
      (node (ref "U$2") (pin "7") (pinfunction "7_7") (pintype "bidirectional"))
    )
    (net (code "147") (name "unconnected-(U$2-Pad8)") (class "Default")
      (node (ref "U$2") (pin "8") (pinfunction "8_8") (pintype "bidirectional"))
    )
    (net (code "148") (name "unconnected-(U$5-5V_1-PadP40)") (class "Default")
      (node (ref "U$5") (pin "P40") (pinfunction "5V_1_P40") (pintype "bidirectional"))
    )
    (net (code "149") (name "unconnected-(U$5-5V_2-PadP20)") (class "Default")
      (node (ref "U$5") (pin "P20") (pinfunction "5V_2_P20") (pintype "bidirectional"))
    )
    (net (code "150") (name "unconnected-(U$5-PA2{slash}PQ3-PadP54)") (class "Default")
      (node (ref "U$5") (pin "P54") (pinfunction "PA2/PQ3_P54") (pintype "bidirectional"))
    )
    (net (code "151") (name "unconnected-(U$5-PA3{slash}PQ2-PadP55)") (class "Default")
      (node (ref "U$5") (pin "P55") (pinfunction "PA3/PQ2_P55") (pintype "bidirectional"))
    )
    (net (code "152") (name "unconnected-(U$5-PB2-PadP22)") (class "Default")
      (node (ref "U$5") (pin "P22") (pinfunction "PB2_P22") (pintype "bidirectional"))
    )
    (net (code "153") (name "unconnected-(U$5-PB3-PadP21)") (class "Default")
      (node (ref "U$5") (pin "P21") (pinfunction "PB3_P21") (pintype "bidirectional"))
    )
    (net (code "154") (name "unconnected-(U$5-PB4-PadP18)") (class "Default")
      (node (ref "U$5") (pin "P18") (pinfunction "PB4_P18") (pintype "bidirectional"))
    )
    (net (code "155") (name "unconnected-(U$5-PB5-PadP17)") (class "Default")
      (node (ref "U$5") (pin "P17") (pinfunction "PB5_P17") (pintype "bidirectional"))
    )
    (net (code "156") (name "unconnected-(U$5-PD0-PadP74)") (class "Default")
      (node (ref "U$5") (pin "P74") (pinfunction "PD0_P74") (pintype "bidirectional"))
    )
    (net (code "157") (name "unconnected-(U$5-PD1-PadP75)") (class "Default")
      (node (ref "U$5") (pin "P75") (pinfunction "PD1_P75") (pintype "bidirectional"))
    )
    (net (code "158") (name "unconnected-(U$5-PD2-PadP9)") (class "Default")
      (node (ref "U$5") (pin "P9") (pinfunction "PD2_P9") (pintype "bidirectional"))
    )
    (net (code "159") (name "unconnected-(U$5-PD3-PadP24)") (class "Default")
      (node (ref "U$5") (pin "P24") (pinfunction "PD3_P24") (pintype "bidirectional"))
    )
    (net (code "160") (name "unconnected-(U$5-PD7-PadP34)") (class "Default")
      (node (ref "U$5") (pin "P34") (pinfunction "PD7_P34") (pintype "bidirectional"))
    )
    (net (code "161") (name "unconnected-(U$5-PE2-PadP36)") (class "Default")
      (node (ref "U$5") (pin "P36") (pinfunction "PE2_P36") (pintype "bidirectional"))
    )
    (net (code "162") (name "unconnected-(U$5-PE3-PadP35)") (class "Default")
      (node (ref "U$5") (pin "P35") (pinfunction "PE3_P35") (pintype "bidirectional"))
    )
    (net (code "163") (name "unconnected-(U$5-PE4-PadP29)") (class "Default")
      (node (ref "U$5") (pin "P29") (pinfunction "PE4_P29") (pintype "bidirectional"))
    )
    (net (code "164") (name "unconnected-(U$5-PE5-PadP25)") (class "Default")
      (node (ref "U$5") (pin "P25") (pinfunction "PE5_P25") (pintype "bidirectional"))
    )
    (net (code "165") (name "unconnected-(U$5-PF1-PadP70)") (class "Default")
      (node (ref "U$5") (pin "P70") (pinfunction "PF1_P70") (pintype "bidirectional"))
    )
    (net (code "166") (name "unconnected-(U$5-PF2-PadP69)") (class "Default")
      (node (ref "U$5") (pin "P69") (pinfunction "PF2_P69") (pintype "bidirectional"))
    )
    (net (code "167") (name "unconnected-(U$5-PF3-PadP68)") (class "Default")
      (node (ref "U$5") (pin "P68") (pinfunction "PF3_P68") (pintype "bidirectional"))
    )
    (net (code "168") (name "unconnected-(U$5-PG0-PadP67)") (class "Default")
      (node (ref "U$5") (pin "P67") (pinfunction "PG0_P67") (pintype "bidirectional"))
    )
    (net (code "169") (name "unconnected-(U$5-PG1-PadP50)") (class "Default")
      (node (ref "U$5") (pin "P50") (pinfunction "PG1_P50") (pintype "bidirectional"))
    )
    (net (code "170") (name "unconnected-(U$5-PH2-PadP78)") (class "Default")
      (node (ref "U$5") (pin "P78") (pinfunction "PH2_P78") (pintype "bidirectional"))
    )
    (net (code "171") (name "unconnected-(U$5-PH3-PadP77)") (class "Default")
      (node (ref "U$5") (pin "P77") (pinfunction "PH3_P77") (pintype "bidirectional"))
    )
    (net (code "172") (name "unconnected-(U$5-PK4-PadP49)") (class "Default")
      (node (ref "U$5") (pin "P49") (pinfunction "PK4_P49") (pintype "bidirectional"))
    )
    (net (code "173") (name "unconnected-(U$5-PK5-PadP48)") (class "Default")
      (node (ref "U$5") (pin "P48") (pinfunction "PK5_P48") (pintype "bidirectional"))
    )
    (net (code "174") (name "unconnected-(U$5-PK6-PadP42)") (class "Default")
      (node (ref "U$5") (pin "P42") (pinfunction "PK6_P42") (pintype "bidirectional"))
    )
    (net (code "175") (name "unconnected-(U$5-PK7-PadP41)") (class "Default")
      (node (ref "U$5") (pin "P41") (pinfunction "PK7_P41") (pintype "bidirectional"))
    )
    (net (code "176") (name "unconnected-(U$5-PL2-PadP62)") (class "Default")
      (node (ref "U$5") (pin "P62") (pinfunction "PL2_P62") (pintype "bidirectional"))
    )
    (net (code "177") (name "unconnected-(U$5-PL3-PadP61)") (class "Default")
      (node (ref "U$5") (pin "P61") (pinfunction "PL3_P61") (pintype "bidirectional"))
    )
    (net (code "178") (name "unconnected-(U$5-PL4-PadP66)") (class "Default")
      (node (ref "U$5") (pin "P66") (pinfunction "PL4_P66") (pintype "bidirectional"))
    )
    (net (code "179") (name "unconnected-(U$5-PM0-PadP47)") (class "Default")
      (node (ref "U$5") (pin "P47") (pinfunction "PM0_P47") (pintype "bidirectional"))
    )
    (net (code "180") (name "unconnected-(U$5-PM1-PadP46)") (class "Default")
      (node (ref "U$5") (pin "P46") (pinfunction "PM1_P46") (pintype "bidirectional"))
    )
    (net (code "181") (name "unconnected-(U$5-PM2-PadP45)") (class "Default")
      (node (ref "U$5") (pin "P45") (pinfunction "PM2_P45") (pintype "bidirectional"))
    )
    (net (code "182") (name "unconnected-(U$5-PM3-PadP79)") (class "Default")
      (node (ref "U$5") (pin "P79") (pinfunction "PM3_P79") (pintype "bidirectional"))
    )
    (net (code "183") (name "unconnected-(U$5-PM4-PadP32)") (class "Default")
      (node (ref "U$5") (pin "P32") (pinfunction "PM4_P32") (pintype "bidirectional"))
    )
    (net (code "184") (name "unconnected-(U$5-PM5-PadP31)") (class "Default")
      (node (ref "U$5") (pin "P31") (pinfunction "PM5_P31") (pintype "bidirectional"))
    )
    (net (code "185") (name "unconnected-(U$5-PN2-PadP73)") (class "Default")
      (node (ref "U$5") (pin "P73") (pinfunction "PN2_P73") (pintype "bidirectional"))
    )
    (net (code "186") (name "unconnected-(U$5-PN3-PadP72)") (class "Default")
      (node (ref "U$5") (pin "P72") (pinfunction "PN3_P72") (pintype "bidirectional"))
    )
    (net (code "187") (name "unconnected-(U$5-PN4-PadP1)") (class "Default")
      (node (ref "U$5") (pin "P1") (pinfunction "PN4_P1") (pintype "bidirectional"))
    )
    (net (code "188") (name "unconnected-(U$5-PN5-PadP2)") (class "Default")
      (node (ref "U$5") (pin "P2") (pinfunction "PN5_P2") (pintype "bidirectional"))
    )
    (net (code "189") (name "unconnected-(U$5-PP2-PadP71)") (class "Default")
      (node (ref "U$5") (pin "P71") (pinfunction "PP2_P71") (pintype "bidirectional"))
    )
    (net (code "190") (name "unconnected-(U$5-PP3-PadP53)") (class "Default")
      (node (ref "U$5") (pin "P53") (pinfunction "PP3_P53") (pintype "bidirectional"))
    )
    (net (code "191") (name "unconnected-(U$5-PP4-PadP3)") (class "Default")
      (node (ref "U$5") (pin "P3") (pinfunction "PP4_P3") (pintype "bidirectional"))
    )
    (net (code "192") (name "unconnected-(U$5-PP5-PadP58)") (class "Default")
      (node (ref "U$5") (pin "P58") (pinfunction "PP5_P58") (pintype "bidirectional"))
    )
    (net (code "193") (name "unconnected-(U$5-PQ0-PadP4)") (class "Default")
      (node (ref "U$5") (pin "P4") (pinfunction "PQ0_P4") (pintype "bidirectional"))
    )
    (net (code "194") (name "unconnected-(U$5-PQ1-PadP52)") (class "Default")
      (node (ref "U$5") (pin "P52") (pinfunction "PQ1_P52") (pintype "bidirectional"))
    )
    (net (code "195") (name "unconnected-(U$5-RST_1-PadP76)") (class "Default")
      (node (ref "U$5") (pin "P76") (pinfunction "RST_1_P76") (pintype "bidirectional"))
    )
    (net (code "196") (name "unconnected-(U$5-RST_2-PadP56)") (class "Default")
      (node (ref "U$5") (pin "P56") (pinfunction "RST_2_P56") (pintype "bidirectional"))
    )
    (net (code "197") (name "unconnected-(U3_MUX-1Y0-Pad12)") (class "Default")
      (node (ref "U3_MUX") (pin "12") (pinfunction "1Y0_12") (pintype "bidirectional"))
    )
    (net (code "198") (name "unconnected-(U3_MUX-2Y0-Pad1)") (class "Default")
      (node (ref "U3_MUX") (pin "1") (pinfunction "2Y0_1") (pintype "bidirectional"))
    )
    (net (code "199") (name "unconnected-(U4_MUX-1Y0-Pad12)") (class "Default")
      (node (ref "U4_MUX") (pin "12") (pinfunction "1Y0_12") (pintype "bidirectional"))
    )
    (net (code "200") (name "unconnected-(U4_MUX-2Y0-Pad1)") (class "Default")
      (node (ref "U4_MUX") (pin "1") (pinfunction "2Y0_1") (pintype "bidirectional"))
    )
  )
)
